# SniperBoard.net
KiCad netlist of a schematic drawn in EAGLE
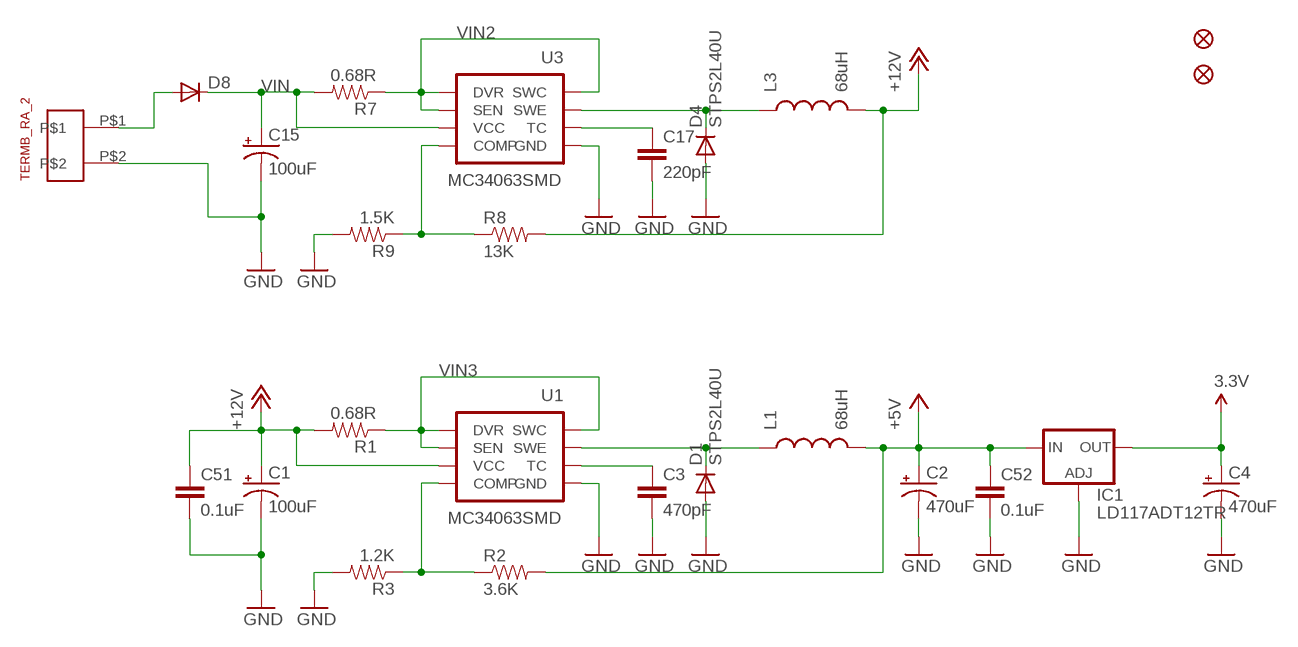
[diagram p0: schematic, sheet 1]
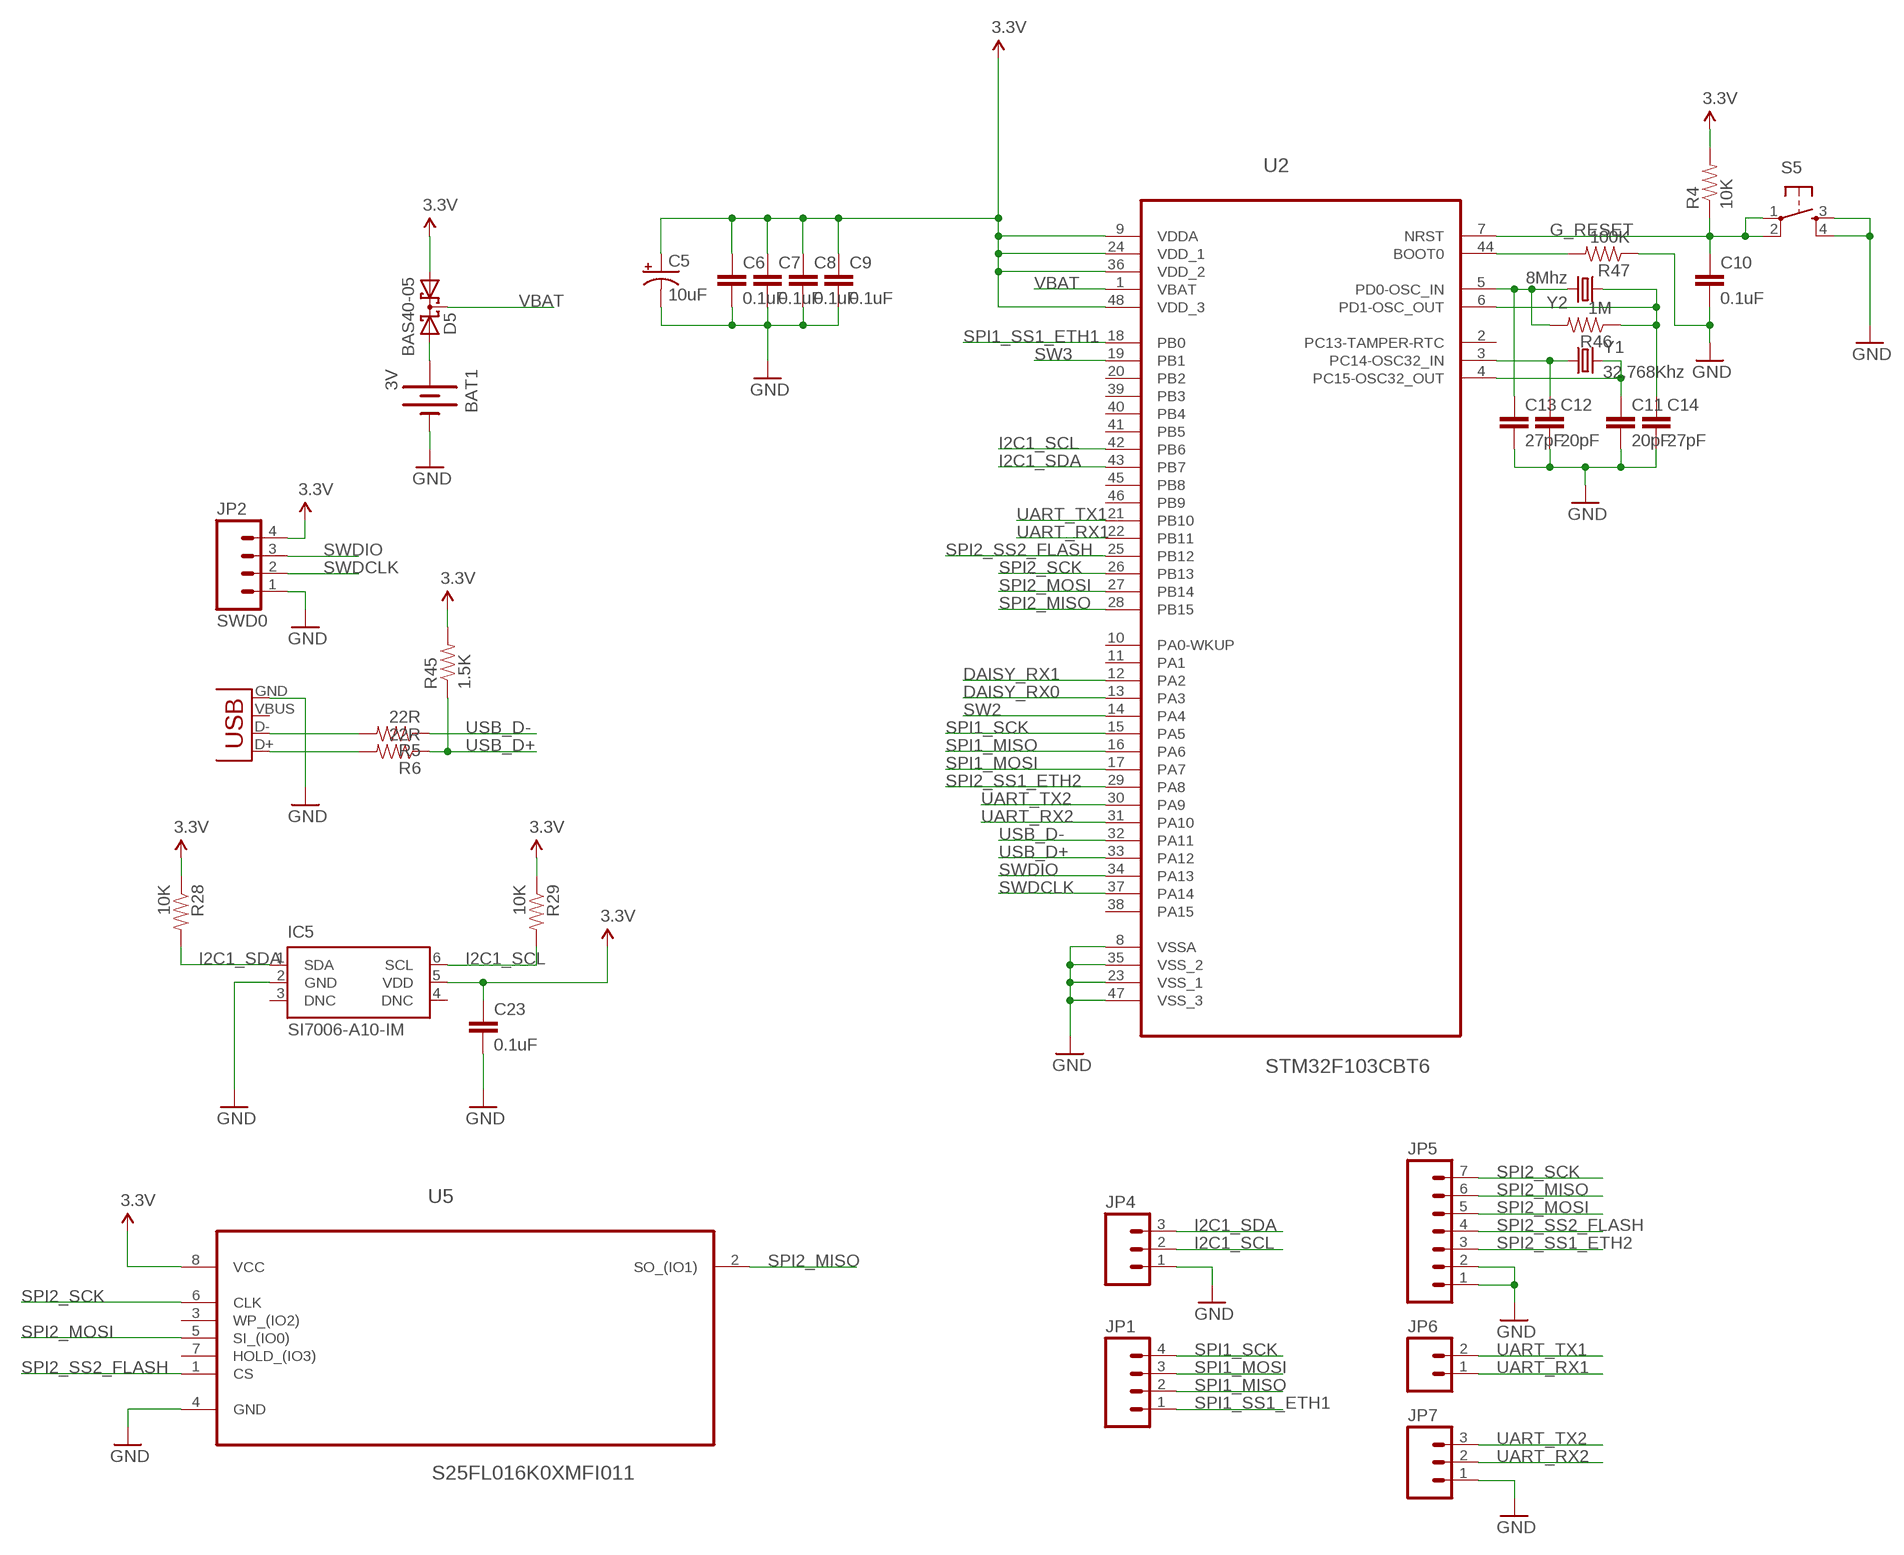
[diagram p1: schematic, sheet 2]
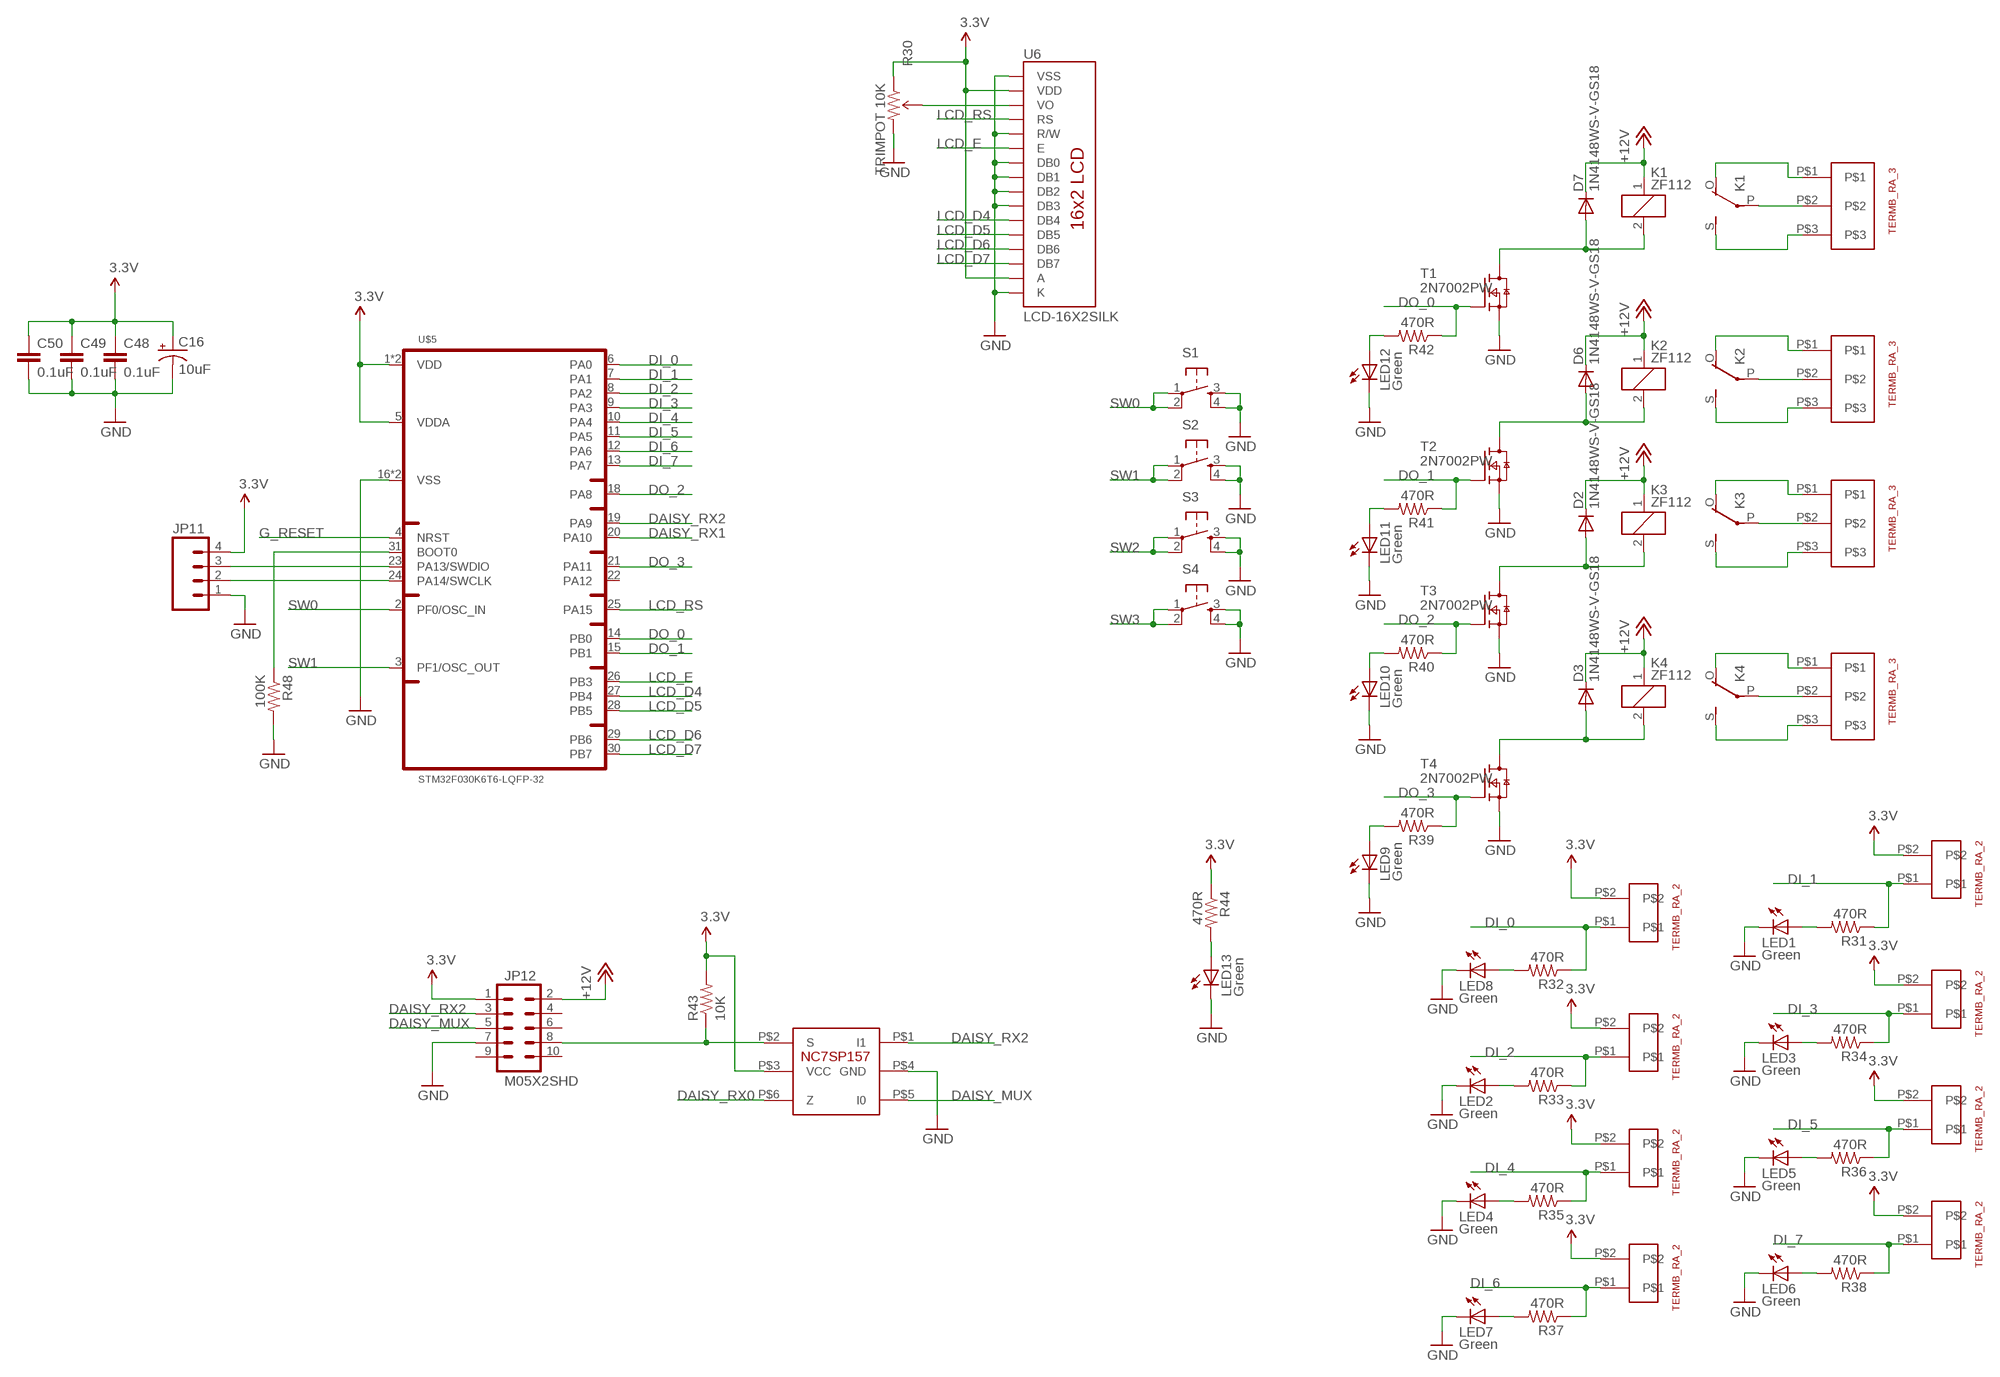
[diagram p2: schematic, sheet 3]
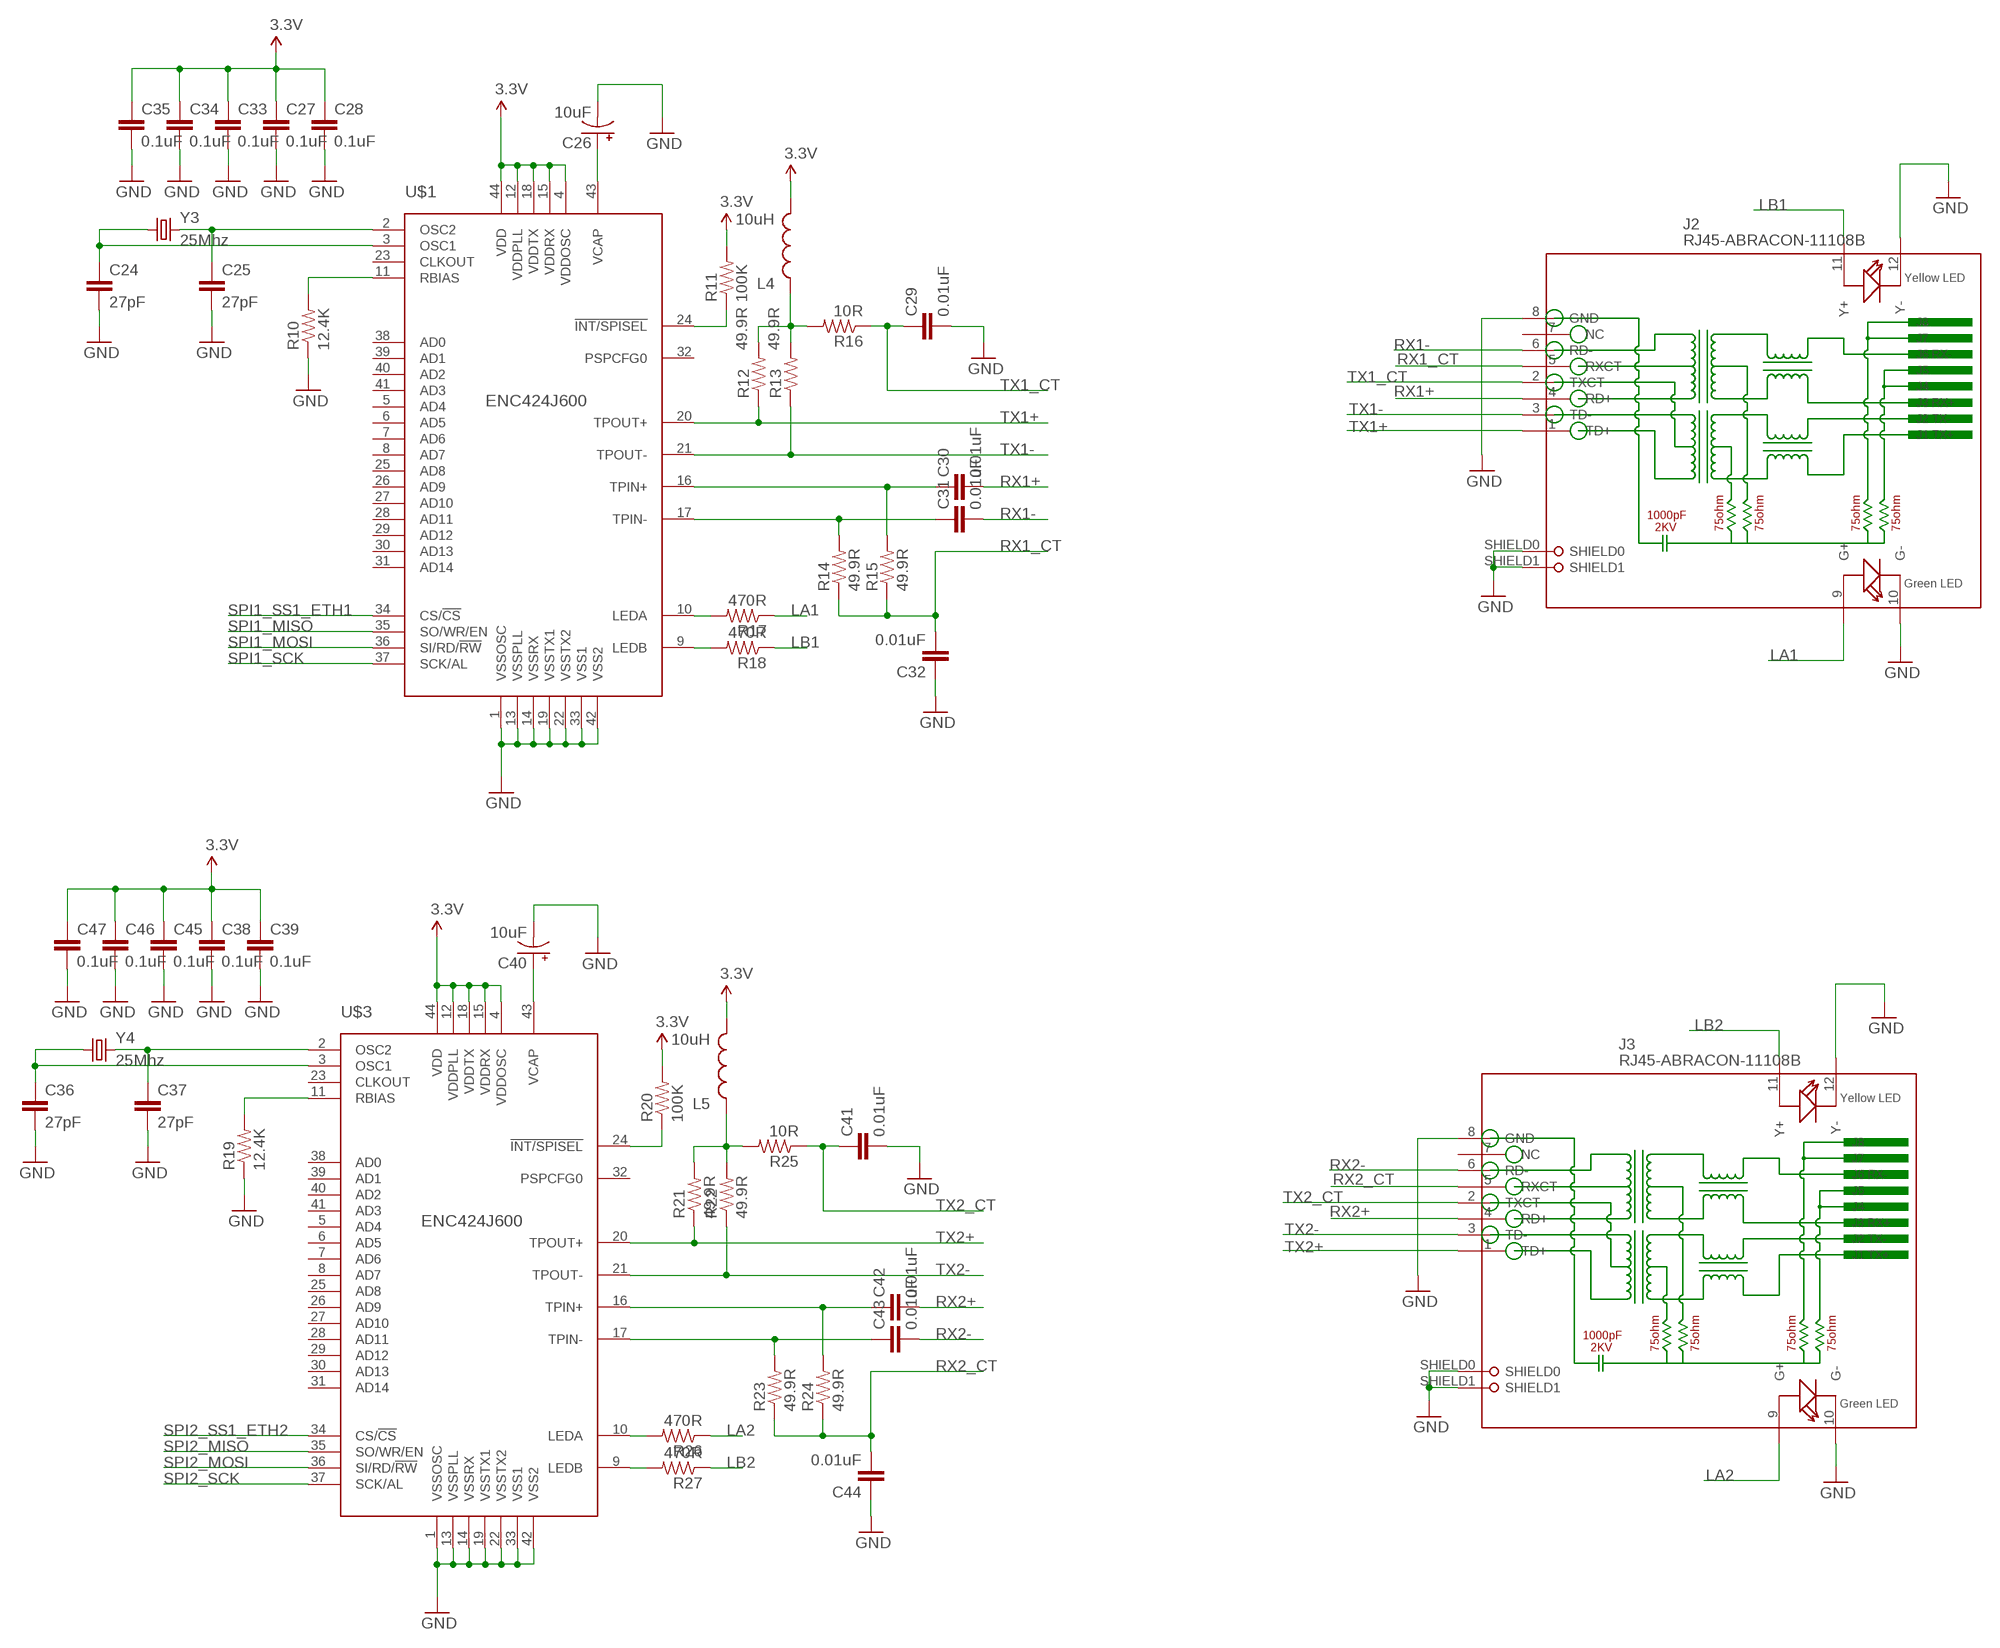
[diagram p3: schematic, sheet 4]
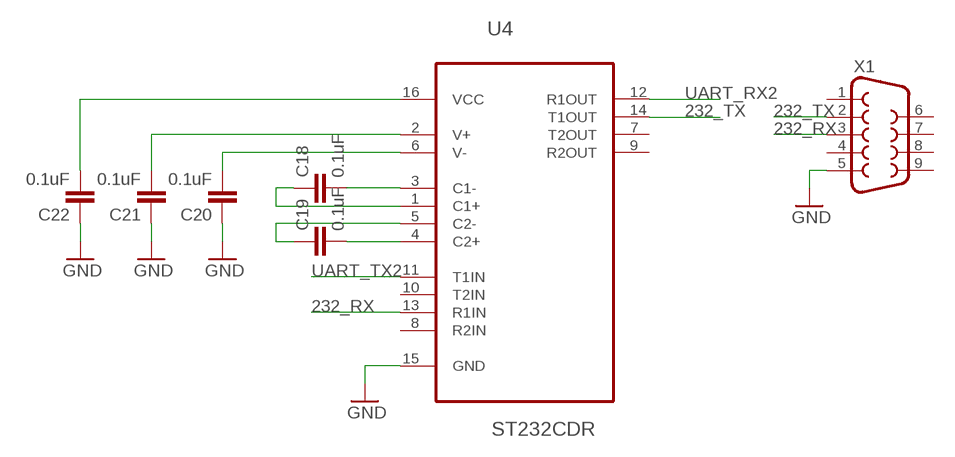
[diagram p4: schematic, sheet 5]

(export (version "E")
  (design (tool "Eeschema 10.0.6"))
  (components
    (comp (ref "C1")
      (value "100uF")
      (footprint "eagle-import:CPOL-RADIAL-100UF-25V")
      (libsource (lib "eagle-import") (part "CAP_POLPTH1"))
    )
    (comp (ref "C2")
      (value "470uF")
      (footprint "eagle-import:CPOL-RADIAL-100UF-25V")
      (libsource (lib "eagle-import") (part "CAP_POLPTH1"))
    )
    (comp (ref "C3")
      (value "470pF")
      (footprint "eagle-import:0805")
      (libsource (lib "eagle-import") (part "SparkFun-Passives_CAP0805"))
    )
    (comp (ref "C4")
      (value "470uF")
      (footprint "eagle-import:CPOL-RADIAL-100UF-25V")
      (libsource (lib "eagle-import") (part "CAP_POLPTH1"))
    )
    (comp (ref "C15")
      (value "100uF")
      (footprint "eagle-import:CPOL-RADIAL-100UF-25V")
      (libsource (lib "eagle-import") (part "CAP_POLPTH1"))
    )
    (comp (ref "C17")
      (value "220pF")
      (footprint "eagle-import:0805")
      (libsource (lib "eagle-import") (part "SparkFun-Passives_CAP0805"))
    )
    (comp (ref "C51")
      (value "0.1uF")
      (footprint "eagle-import:0805")
      (libsource (lib "eagle-import") (part "CAP0805"))
    )
    (comp (ref "C52")
      (value "0.1uF")
      (footprint "eagle-import:0805")
      (libsource (lib "eagle-import") (part "CAP0805"))
    )
    (comp (ref "D1")
      (value "STPS2L40U")
      (footprint "eagle-import:SMA-DIODE")
      (libsource (lib "eagle-import") (part "DIODESMA"))
    )
    (comp (ref "D4")
      (value "STPS2L40U")
      (footprint "eagle-import:SMA-DIODE")
      (libsource (lib "eagle-import") (part "DIODESMA"))
    )
    (comp (ref "D8")
      (value "DIODESMB")
      (footprint "eagle-import:SMB-DIODE")
      (libsource (lib "eagle-import") (part "DIODESMB"))
    )
    (comp (ref "FID1")
      (value "FIDUCIAL1.5X3")
      (footprint "eagle-import:FIDUCIAL-1.5X3")
      (libsource (lib "eagle-import") (part "FIDUCIAL1.5X3"))
    )
    (comp (ref "FID2")
      (value "FIDUCIAL1.5X3")
      (footprint "eagle-import:FIDUCIAL-1.5X3")
      (libsource (lib "eagle-import") (part "FIDUCIAL1.5X3"))
    )
    (comp (ref "IC1")
      (value "LD117ADT12TR")
      (footprint "eagle-import:DPACK")
      (libsource (lib "eagle-import") (part "LD117A?DT12TR"))
    )
    (comp (ref "L1")
      (value "68uH")
      (footprint "eagle-import:CDRH125")
      (libsource (lib "eagle-import") (part "INDUCTORPWR"))
    )
    (comp (ref "L3")
      (value "68uH")
      (footprint "eagle-import:CDRH125")
      (libsource (lib "eagle-import") (part "INDUCTORPWR"))
    )
    (comp (ref "R1")
      (value "0.68R")
      (footprint "eagle-import:0805")
      (libsource (lib "eagle-import") (part "RESISTOR0805-RES"))
    )
    (comp (ref "R2")
      (value "3.6K")
      (footprint "eagle-import:0805")
      (libsource (lib "eagle-import") (part "RESISTOR0805-RES"))
    )
    (comp (ref "R3")
      (value "1.2K")
      (footprint "eagle-import:0805")
      (libsource (lib "eagle-import") (part "RESISTOR0805-RES"))
    )
    (comp (ref "R7")
      (value "0.68R")
      (footprint "eagle-import:0805")
      (libsource (lib "eagle-import") (part "RESISTOR0805-RES"))
    )
    (comp (ref "R8")
      (value "13K")
      (footprint "eagle-import:0805")
      (libsource (lib "eagle-import") (part "RESISTOR0805-RES"))
    )
    (comp (ref "R9")
      (value "1.5K")
      (footprint "eagle-import:0805")
      (libsource (lib "eagle-import") (part "RESISTOR0805-RES"))
    )
    (comp (ref "U$2")
      (value "1X02_TERMB_RA")
      (footprint "eagle-import:1X02_TERMB_RA")
      (libsource (lib "eagle-import") (part "1X02_TERMB_RA"))
    )
    (comp (ref "U1")
      (value "MC34063SMD")
      (footprint "eagle-import:SO08")
      (libsource (lib "eagle-import") (part "MC34063SMD"))
    )
    (comp (ref "U3")
      (value "MC34063SMD")
      (footprint "eagle-import:SO08")
      (libsource (lib "eagle-import") (part "MC34063SMD"))
    )
    (comp (ref "C18")
      (value "0.1uF")
      (footprint "eagle-import:0805")
      (libsource (lib "eagle-import") (part "SparkFun-Passives_CAP0805"))
    )
    (comp (ref "C19")
      (value "0.1uF")
      (footprint "eagle-import:0805")
      (libsource (lib "eagle-import") (part "SparkFun-Passives_CAP0805"))
    )
    (comp (ref "C20")
      (value "0.1uF")
      (footprint "eagle-import:0805")
      (libsource (lib "eagle-import") (part "SparkFun-Passives_CAP0805"))
    )
    (comp (ref "C21")
      (value "0.1uF")
      (footprint "eagle-import:0805")
      (libsource (lib "eagle-import") (part "SparkFun-Passives_CAP0805"))
    )
    (comp (ref "C22")
      (value "0.1uF")
      (footprint "eagle-import:0805")
      (libsource (lib "eagle-import") (part "SparkFun-Passives_CAP0805"))
    )
    (comp (ref "U4")
      (value "ST232CDR")
      (footprint "eagle-import:SOIC127P600X175-16N")
      (libsource (lib "eagle-import") (part "ST232CDR"))
    )
    (comp (ref "X1")
      (value "DB9FEMALE")
      (footprint "eagle-import:DB9")
      (libsource (lib "eagle-import") (part "DB9FEMALE"))
    )
    (comp (ref "BAT1")
      (value "3V")
      (footprint "eagle-import:BATTCOM_20MM_PTH")
      (libsource (lib "eagle-import") (part "BATTERY20PTH"))
    )
    (comp (ref "C5")
      (value "10uF")
      (footprint "eagle-import:EIA3216")
      (libsource (lib "eagle-import") (part "10UF-TANT"))
    )
    (comp (ref "C6")
      (value "0.1uF")
      (footprint "eagle-import:0805")
      (libsource (lib "eagle-import") (part "CAP0805"))
    )
    (comp (ref "C7")
      (value "0.1uF")
      (footprint "eagle-import:0805")
      (libsource (lib "eagle-import") (part "CAP0805"))
    )
    (comp (ref "C8")
      (value "0.1uF")
      (footprint "eagle-import:0805")
      (libsource (lib "eagle-import") (part "CAP0805"))
    )
    (comp (ref "C9")
      (value "0.1uF")
      (footprint "eagle-import:0805")
      (libsource (lib "eagle-import") (part "CAP0805"))
    )
    (comp (ref "C10")
      (value "0.1uF")
      (footprint "eagle-import:0805")
      (libsource (lib "eagle-import") (part "CAP0805"))
    )
    (comp (ref "C11")
      (value "20pF")
      (footprint "eagle-import:0805")
      (libsource (lib "eagle-import") (part "CAP0805"))
    )
    (comp (ref "C12")
      (value "20pF")
      (footprint "eagle-import:0805")
      (libsource (lib "eagle-import") (part "CAP0805"))
    )
    (comp (ref "C13")
      (value "27pF")
      (footprint "eagle-import:0805")
      (libsource (lib "eagle-import") (part "CAP0805"))
    )
    (comp (ref "C14")
      (value "27pF")
      (footprint "eagle-import:0805")
      (libsource (lib "eagle-import") (part "CAP0805"))
    )
    (comp (ref "C23")
      (value "0.1uF")
      (footprint "eagle-import:0805")
      (libsource (lib "eagle-import") (part "CAP0805"))
    )
    (comp (ref "D5")
      (value "BAS40-05")
      (footprint "eagle-import:SOT23")
      (libsource (lib "eagle-import") (part "BAS40-05"))
    )
    (comp (ref "IC5")
      (value "SI7006-A10-IM")
      (footprint "eagle-import:DFN6-3X3")
      (fields (field (name "MF") "Silicon Labs") (field (name "MPN") "Si7006-A10-IM"))
      (libsource (lib "eagle-import") (part "SI7006-A10-IM"))
    )
    (comp (ref "JP1")
      (value "M04PTH")
      (footprint "eagle-import:1X04")
      (libsource (lib "eagle-import") (part "M04PTH"))
    )
    (comp (ref "JP2")
      (value "SWD0")
      (footprint "eagle-import:1X04")
      (libsource (lib "eagle-import") (part "M04PTH"))
    )
    (comp (ref "JP3")
      (value "USB-B")
      (footprint "eagle-import:USB-B-PTH")
      (libsource (lib "eagle-import") (part "USBPTH"))
    )
    (comp (ref "JP4")
      (value "M03PTH")
      (footprint "eagle-import:1X03")
      (libsource (lib "eagle-import") (part "M03PTH"))
    )
    (comp (ref "JP5")
      (value "M07")
      (footprint "eagle-import:1X07")
      (libsource (lib "eagle-import") (part "M07"))
    )
    (comp (ref "JP6")
      (value "M02PTH")
      (footprint "eagle-import:1X02")
      (libsource (lib "eagle-import") (part "M02PTH"))
    )
    (comp (ref "JP7")
      (value "M03PTH")
      (footprint "eagle-import:1X03")
      (libsource (lib "eagle-import") (part "M03PTH"))
    )
    (comp (ref "R4")
      (value "10K")
      (footprint "eagle-import:0805")
      (libsource (lib "eagle-import") (part "SparkFun-Resistors_RESISTOR0805-RES"))
    )
    (comp (ref "R5")
      (value "22R")
      (footprint "eagle-import:0805")
      (libsource (lib "eagle-import") (part "SparkFun-Resistors_RESISTOR0805-RES"))
    )
    (comp (ref "R6")
      (value "22R")
      (footprint "eagle-import:0805")
      (libsource (lib "eagle-import") (part "SparkFun-Resistors_RESISTOR0805-RES"))
    )
    (comp (ref "R28")
      (value "10K")
      (footprint "eagle-import:0805")
      (libsource (lib "eagle-import") (part "SparkFun-Resistors_RESISTOR0805-RES"))
    )
    (comp (ref "R29")
      (value "10K")
      (footprint "eagle-import:0805")
      (libsource (lib "eagle-import") (part "SparkFun-Resistors_RESISTOR0805-RES"))
    )
    (comp (ref "R45")
      (value "1.5K")
      (footprint "eagle-import:0805")
      (libsource (lib "eagle-import") (part "SparkFun-Resistors_RESISTOR0805-RES"))
    )
    (comp (ref "R46")
      (value "1M")
      (footprint "eagle-import:0805")
      (libsource (lib "eagle-import") (part "SparkFun-Resistors_RESISTOR0805-RES"))
    )
    (comp (ref "R47")
      (value "100K")
      (footprint "eagle-import:0805")
      (libsource (lib "eagle-import") (part "SparkFun-Resistors_RESISTOR0805-RES"))
    )
    (comp (ref "S5")
      (value "TAC_SWITCHPTH")
      (footprint "eagle-import:TACTILE-PTH")
      (libsource (lib "eagle-import") (part "TAC_SWITCHPTH"))
    )
    (comp (ref "U2")
      (value "STM32F103CBT6")
      (footprint "eagle-import:QFP50P900X900X160-48N")
      (libsource (lib "eagle-import") (part "STM32F103CBT6"))
    )
    (comp (ref "U5")
      (value "S25FL016K0XMFI011")
      (footprint "eagle-import:SOIC127P800X215-8N")
      (libsource (lib "eagle-import") (part "S25FL016K0XMFI011"))
    )
    (comp (ref "Y1")
      (value "32.768Khz")
      (footprint "eagle-import:MC-306")
      (fields (field (name "MPN") "MC-306 60.0KHZ  100PPM ,12.5PF"))
      (libsource (lib "eagle-import") (part "MC-306"))
    )
    (comp (ref "Y2")
      (value "8Mhz")
      (footprint "eagle-import:HC49US")
      (libsource (lib "eagle-import") (part "CRYSTALHC49US"))
    )
    (comp (ref "C16")
      (value "10uF")
      (footprint "eagle-import:EIA3216")
      (libsource (lib "eagle-import") (part "10UF-TANT"))
    )
    (comp (ref "C48")
      (value "0.1uF")
      (footprint "eagle-import:0805")
      (libsource (lib "eagle-import") (part "CAP0805"))
    )
    (comp (ref "C49")
      (value "0.1uF")
      (footprint "eagle-import:0805")
      (libsource (lib "eagle-import") (part "CAP0805"))
    )
    (comp (ref "C50")
      (value "0.1uF")
      (footprint "eagle-import:0805")
      (libsource (lib "eagle-import") (part "CAP0805"))
    )
    (comp (ref "D2")
      (value "1N4148WS-V-GS18")
      (footprint "eagle-import:SMA-DIODE_ALT")
      (libsource (lib "eagle-import") (part "DIODESMA-ALT"))
    )
    (comp (ref "D3")
      (value "1N4148WS-V-GS18")
      (footprint "eagle-import:SMA-DIODE_ALT")
      (libsource (lib "eagle-import") (part "DIODESMA-ALT"))
    )
    (comp (ref "D6")
      (value "1N4148WS-V-GS18")
      (footprint "eagle-import:SMA-DIODE_ALT")
      (libsource (lib "eagle-import") (part "DIODESMA-ALT"))
    )
    (comp (ref "D7")
      (value "1N4148WS-V-GS18")
      (footprint "eagle-import:SMA-DIODE_ALT")
      (libsource (lib "eagle-import") (part "DIODESMA-ALT"))
    )
    (comp (ref "JP11")
      (value "M04PTH")
      (footprint "eagle-import:1X04")
      (libsource (lib "eagle-import") (part "M04PTH"))
    )
    (comp (ref "JP12")
      (value "M05X2SHD")
      (footprint "eagle-import:2X5-SHROUDED")
      (libsource (lib "eagle-import") (part "M05X2SHD"))
    )
    (comp (ref "K1")
      (value "ZF112")
      (footprint "eagle-import:ZF112")
      (libsource (lib "eagle-import") (part "ZF112"))
    )
    (comp (ref "K2")
      (value "ZF112")
      (footprint "eagle-import:ZF112")
      (libsource (lib "eagle-import") (part "ZF112"))
    )
    (comp (ref "K3")
      (value "ZF112")
      (footprint "eagle-import:ZF112")
      (libsource (lib "eagle-import") (part "ZF112"))
    )
    (comp (ref "K4")
      (value "ZF112")
      (footprint "eagle-import:ZF112")
      (libsource (lib "eagle-import") (part "ZF112"))
    )
    (comp (ref "LED1")
      (value "Green")
      (footprint "eagle-import:LED-1206")
      (libsource (lib "eagle-import") (part "LED1206"))
    )
    (comp (ref "LED2")
      (value "Green")
      (footprint "eagle-import:LED-1206")
      (libsource (lib "eagle-import") (part "LED1206"))
    )
    (comp (ref "LED3")
      (value "Green")
      (footprint "eagle-import:LED-1206")
      (libsource (lib "eagle-import") (part "LED1206"))
    )
    (comp (ref "LED4")
      (value "Green")
      (footprint "eagle-import:LED-1206")
      (libsource (lib "eagle-import") (part "LED1206"))
    )
    (comp (ref "LED5")
      (value "Green")
      (footprint "eagle-import:LED-1206")
      (libsource (lib "eagle-import") (part "LED1206"))
    )
    (comp (ref "LED6")
      (value "Green")
      (footprint "eagle-import:LED-1206")
      (libsource (lib "eagle-import") (part "LED1206"))
    )
    (comp (ref "LED7")
      (value "Green")
      (footprint "eagle-import:LED-1206")
      (libsource (lib "eagle-import") (part "LED1206"))
    )
    (comp (ref "LED8")
      (value "Green")
      (footprint "eagle-import:LED-1206")
      (libsource (lib "eagle-import") (part "LED1206"))
    )
    (comp (ref "LED9")
      (value "Green")
      (footprint "eagle-import:LED-1206")
      (libsource (lib "eagle-import") (part "LED1206"))
    )
    (comp (ref "LED10")
      (value "Green")
      (footprint "eagle-import:LED-1206")
      (libsource (lib "eagle-import") (part "LED1206"))
    )
    (comp (ref "LED11")
      (value "Green")
      (footprint "eagle-import:LED-1206")
      (libsource (lib "eagle-import") (part "LED1206"))
    )
    (comp (ref "LED12")
      (value "Green")
      (footprint "eagle-import:LED-1206")
      (libsource (lib "eagle-import") (part "LED1206"))
    )
    (comp (ref "LED13")
      (value "Green")
      (footprint "eagle-import:LED-1206")
      (libsource (lib "eagle-import") (part "LED1206"))
    )
    (comp (ref "R30")
      (value "TRIMPOT 10K")
      (footprint "eagle-import:TRIM_POT_PTH")
      (libsource (lib "eagle-import") (part "TRIMPOTPTH"))
    )
    (comp (ref "R31")
      (value "470R")
      (footprint "eagle-import:0805")
      (libsource (lib "eagle-import") (part "RESISTOR0805-RES"))
    )
    (comp (ref "R32")
      (value "470R")
      (footprint "eagle-import:0805")
      (libsource (lib "eagle-import") (part "RESISTOR0805-RES"))
    )
    (comp (ref "R33")
      (value "470R")
      (footprint "eagle-import:0805")
      (libsource (lib "eagle-import") (part "RESISTOR0805-RES"))
    )
    (comp (ref "R34")
      (value "470R")
      (footprint "eagle-import:0805")
      (libsource (lib "eagle-import") (part "RESISTOR0805-RES"))
    )
    (comp (ref "R35")
      (value "470R")
      (footprint "eagle-import:0805")
      (libsource (lib "eagle-import") (part "RESISTOR0805-RES"))
    )
    (comp (ref "R36")
      (value "470R")
      (footprint "eagle-import:0805")
      (libsource (lib "eagle-import") (part "RESISTOR0805-RES"))
    )
    (comp (ref "R37")
      (value "470R")
      (footprint "eagle-import:0805")
      (libsource (lib "eagle-import") (part "RESISTOR0805-RES"))
    )
    (comp (ref "R38")
      (value "470R")
      (footprint "eagle-import:0805")
      (libsource (lib "eagle-import") (part "RESISTOR0805-RES"))
    )
    (comp (ref "R39")
      (value "470R")
      (footprint "eagle-import:0805")
      (libsource (lib "eagle-import") (part "RESISTOR0805-RES"))
    )
    (comp (ref "R40")
      (value "470R")
      (footprint "eagle-import:0805")
      (libsource (lib "eagle-import") (part "RESISTOR0805-RES"))
    )
    (comp (ref "R41")
      (value "470R")
      (footprint "eagle-import:0805")
      (libsource (lib "eagle-import") (part "RESISTOR0805-RES"))
    )
    (comp (ref "R42")
      (value "470R")
      (footprint "eagle-import:0805")
      (libsource (lib "eagle-import") (part "RESISTOR0805-RES"))
    )
    (comp (ref "R43")
      (value "10K")
      (footprint "eagle-import:0805")
      (libsource (lib "eagle-import") (part "RESISTOR0805-RES"))
    )
    (comp (ref "R44")
      (value "470R")
      (footprint "eagle-import:0805")
      (libsource (lib "eagle-import") (part "RESISTOR0805-RES"))
    )
    (comp (ref "R48")
      (value "100K")
      (footprint "eagle-import:0805")
      (libsource (lib "eagle-import") (part "RESISTOR0805-RES"))
    )
    (comp (ref "S1")
      (value "TAC_SWITCHPTH")
      (footprint "eagle-import:TACTILE-PTH")
      (libsource (lib "eagle-import") (part "TAC_SWITCHPTH"))
    )
    (comp (ref "S2")
      (value "TAC_SWITCHPTH")
      (footprint "eagle-import:TACTILE-PTH")
      (libsource (lib "eagle-import") (part "TAC_SWITCHPTH"))
    )
    (comp (ref "S3")
      (value "TAC_SWITCHPTH")
      (footprint "eagle-import:TACTILE-PTH")
      (libsource (lib "eagle-import") (part "TAC_SWITCHPTH"))
    )
    (comp (ref "S4")
      (value "TAC_SWITCHPTH")
      (footprint "eagle-import:TACTILE-PTH")
      (libsource (lib "eagle-import") (part "TAC_SWITCHPTH"))
    )
    (comp (ref "T1")
      (value "2N7002PW")
      (footprint "eagle-import:SOT323")
      (libsource (lib "eagle-import") (part "2N7002PW"))
    )
    (comp (ref "T2")
      (value "2N7002PW")
      (footprint "eagle-import:SOT323")
      (libsource (lib "eagle-import") (part "2N7002PW"))
    )
    (comp (ref "T3")
      (value "2N7002PW")
      (footprint "eagle-import:SOT323")
      (libsource (lib "eagle-import") (part "2N7002PW"))
    )
    (comp (ref "T4")
      (value "2N7002PW")
      (footprint "eagle-import:SOT323")
      (libsource (lib "eagle-import") (part "2N7002PW"))
    )
    (comp (ref "U$4")
      (value "NC7SP157")
      (footprint "eagle-import:SC70-6")
      (libsource (lib "eagle-import") (part "NC7SP157"))
    )
    (comp (ref "U$5")
      (value "STM32F030K6T6-LQFP-32")
      (footprint "eagle-import:LQFP-32")
      (libsource (lib "eagle-import") (part "STM32F030K6T6-LQFP-32"))
    )
    (comp (ref "U$6")
      (value "1X02_TERMB_RA")
      (footprint "eagle-import:1X02_TERMB_RA")
      (libsource (lib "eagle-import") (part "1X02_TERMB_RA"))
    )
    (comp (ref "U$7")
      (value "1X02_TERMB_RA")
      (footprint "eagle-import:1X02_TERMB_RA")
      (libsource (lib "eagle-import") (part "1X02_TERMB_RA"))
    )
    (comp (ref "U$8")
      (value "1X02_TERMB_RA")
      (footprint "eagle-import:1X02_TERMB_RA")
      (libsource (lib "eagle-import") (part "1X02_TERMB_RA"))
    )
    (comp (ref "U$9")
      (value "1X02_TERMB_RA")
      (footprint "eagle-import:1X02_TERMB_RA")
      (libsource (lib "eagle-import") (part "1X02_TERMB_RA"))
    )
    (comp (ref "U$10")
      (value "1X02_TERMB_RA")
      (footprint "eagle-import:1X02_TERMB_RA")
      (libsource (lib "eagle-import") (part "1X02_TERMB_RA"))
    )
    (comp (ref "U$11")
      (value "1X02_TERMB_RA")
      (footprint "eagle-import:1X02_TERMB_RA")
      (libsource (lib "eagle-import") (part "1X02_TERMB_RA"))
    )
    (comp (ref "U$12")
      (value "1X02_TERMB_RA")
      (footprint "eagle-import:1X02_TERMB_RA")
      (libsource (lib "eagle-import") (part "1X02_TERMB_RA"))
    )
    (comp (ref "U$13")
      (value "1X02_TERMB_RA")
      (footprint "eagle-import:1X02_TERMB_RA")
      (libsource (lib "eagle-import") (part "1X02_TERMB_RA"))
    )
    (comp (ref "U$14")
      (value "1X03_TERMB_RA")
      (footprint "eagle-import:1X03_TERMB_RA")
      (libsource (lib "eagle-import") (part "1X03_TERMB_RA"))
    )
    (comp (ref "U$15")
      (value "1X03_TERMB_RA")
      (footprint "eagle-import:1X03_TERMB_RA")
      (libsource (lib "eagle-import") (part "1X03_TERMB_RA"))
    )
    (comp (ref "U$16")
      (value "1X03_TERMB_RA")
      (footprint "eagle-import:1X03_TERMB_RA")
      (libsource (lib "eagle-import") (part "1X03_TERMB_RA"))
    )
    (comp (ref "U$17")
      (value "1X03_TERMB_RA")
      (footprint "eagle-import:1X03_TERMB_RA")
      (libsource (lib "eagle-import") (part "1X03_TERMB_RA"))
    )
    (comp (ref "U6")
      (value "LCD-16X2SILK")
      (footprint "eagle-import:LCD-16X2")
      (libsource (lib "eagle-import") (part "LCD-16X2SILK"))
    )
    (comp (ref "C24")
      (value "27pF")
      (footprint "eagle-import:0805")
      (libsource (lib "eagle-import") (part "CAP0805"))
    )
    (comp (ref "C25")
      (value "27pF")
      (footprint "eagle-import:0805")
      (libsource (lib "eagle-import") (part "CAP0805"))
    )
    (comp (ref "C26")
      (value "10uF")
      (footprint "eagle-import:EIA3528-KIT")
      (libsource (lib "eagle-import") (part "CAP_POL3528-KIT"))
    )
    (comp (ref "C27")
      (value "0.1uF")
      (footprint "eagle-import:0805")
      (libsource (lib "eagle-import") (part "CAP0805"))
    )
    (comp (ref "C28")
      (value "0.1uF")
      (footprint "eagle-import:0805")
      (libsource (lib "eagle-import") (part "CAP0805"))
    )
    (comp (ref "C29")
      (value "0.01uF")
      (footprint "eagle-import:0805")
      (libsource (lib "eagle-import") (part "CAP0805"))
    )
    (comp (ref "C30")
      (value "0.01uF")
      (footprint "eagle-import:0805")
      (libsource (lib "eagle-import") (part "CAP0805"))
    )
    (comp (ref "C31")
      (value "0.01uF")
      (footprint "eagle-import:0805")
      (libsource (lib "eagle-import") (part "CAP0805"))
    )
    (comp (ref "C32")
      (value "0.01uF")
      (footprint "eagle-import:0805")
      (libsource (lib "eagle-import") (part "CAP0805"))
    )
    (comp (ref "C33")
      (value "0.1uF")
      (footprint "eagle-import:0805")
      (libsource (lib "eagle-import") (part "CAP0805"))
    )
    (comp (ref "C34")
      (value "0.1uF")
      (footprint "eagle-import:0805")
      (libsource (lib "eagle-import") (part "CAP0805"))
    )
    (comp (ref "C35")
      (value "0.1uF")
      (footprint "eagle-import:0805")
      (libsource (lib "eagle-import") (part "CAP0805"))
    )
    (comp (ref "C36")
      (value "27pF")
      (footprint "eagle-import:0805")
      (libsource (lib "eagle-import") (part "CAP0805"))
    )
    (comp (ref "C37")
      (value "27pF")
      (footprint "eagle-import:0805")
      (libsource (lib "eagle-import") (part "CAP0805"))
    )
    (comp (ref "C38")
      (value "0.1uF")
      (footprint "eagle-import:0805")
      (libsource (lib "eagle-import") (part "CAP0805"))
    )
    (comp (ref "C39")
      (value "0.1uF")
      (footprint "eagle-import:0805")
      (libsource (lib "eagle-import") (part "CAP0805"))
    )
    (comp (ref "C40")
      (value "10uF")
      (footprint "eagle-import:EIA3528-KIT")
      (libsource (lib "eagle-import") (part "CAP_POL3528-KIT"))
    )
    (comp (ref "C41")
      (value "0.01uF")
      (footprint "eagle-import:0805")
      (libsource (lib "eagle-import") (part "CAP0805"))
    )
    (comp (ref "C42")
      (value "0.01uF")
      (footprint "eagle-import:0805")
      (libsource (lib "eagle-import") (part "CAP0805"))
    )
    (comp (ref "C43")
      (value "0.01uF")
      (footprint "eagle-import:0805")
      (libsource (lib "eagle-import") (part "CAP0805"))
    )
    (comp (ref "C44")
      (value "0.01uF")
      (footprint "eagle-import:0805")
      (libsource (lib "eagle-import") (part "CAP0805"))
    )
    (comp (ref "C45")
      (value "0.1uF")
      (footprint "eagle-import:0805")
      (libsource (lib "eagle-import") (part "CAP0805"))
    )
    (comp (ref "C46")
      (value "0.1uF")
      (footprint "eagle-import:0805")
      (libsource (lib "eagle-import") (part "CAP0805"))
    )
    (comp (ref "C47")
      (value "0.1uF")
      (footprint "eagle-import:0805")
      (libsource (lib "eagle-import") (part "CAP0805"))
    )
    (comp (ref "J2")
      (value "RJ45-ABRACON-11108B")
      (footprint "eagle-import:RJ45-ABRACON-111008B")
      (libsource (lib "eagle-import") (part "RJ45-ABRACON-11108B"))
    )
    (comp (ref "J3")
      (value "RJ45-ABRACON-11108B")
      (footprint "eagle-import:RJ45-ABRACON-111008B")
      (libsource (lib "eagle-import") (part "RJ45-ABRACON-11108B"))
    )
    (comp (ref "L4")
      (value "10uH")
      (footprint "eagle-import:0805")
      (libsource (lib "eagle-import") (part "INDUCTOR0805"))
    )
    (comp (ref "L5")
      (value "10uH")
      (footprint "eagle-import:0805")
      (libsource (lib "eagle-import") (part "INDUCTOR0805"))
    )
    (comp (ref "R10")
      (value "12.4K")
      (footprint "eagle-import:0805")
      (libsource (lib "eagle-import") (part "SparkFun-Resistors_RESISTOR0805-RES"))
    )
    (comp (ref "R11")
      (value "100K")
      (footprint "eagle-import:0805")
      (libsource (lib "eagle-import") (part "SparkFun-Resistors_RESISTOR0805-RES"))
    )
    (comp (ref "R12")
      (value "49.9R")
      (footprint "eagle-import:0805")
      (libsource (lib "eagle-import") (part "SparkFun-Resistors_RESISTOR0805-RES"))
    )
    (comp (ref "R13")
      (value "49.9R")
      (footprint "eagle-import:0805")
      (libsource (lib "eagle-import") (part "SparkFun-Resistors_RESISTOR0805-RES"))
    )
    (comp (ref "R14")
      (value "49.9R")
      (footprint "eagle-import:0805")
      (libsource (lib "eagle-import") (part "SparkFun-Resistors_RESISTOR0805-RES"))
    )
    (comp (ref "R15")
      (value "49.9R")
      (footprint "eagle-import:0805")
      (libsource (lib "eagle-import") (part "SparkFun-Resistors_RESISTOR0805-RES"))
    )
    (comp (ref "R16")
      (value "10R")
      (footprint "eagle-import:0805")
      (libsource (lib "eagle-import") (part "SparkFun-Resistors_RESISTOR0805-RES"))
    )
    (comp (ref "R17")
      (value "470R")
      (footprint "eagle-import:0805")
      (libsource (lib "eagle-import") (part "SparkFun-Resistors_RESISTOR0805-RES"))
    )
    (comp (ref "R18")
      (value "470R")
      (footprint "eagle-import:0805")
      (libsource (lib "eagle-import") (part "SparkFun-Resistors_RESISTOR0805-RES"))
    )
    (comp (ref "R19")
      (value "12.4K")
      (footprint "eagle-import:0805")
      (libsource (lib "eagle-import") (part "SparkFun-Resistors_RESISTOR0805-RES"))
    )
    (comp (ref "R20")
      (value "100K")
      (footprint "eagle-import:0805")
      (libsource (lib "eagle-import") (part "SparkFun-Resistors_RESISTOR0805-RES"))
    )
    (comp (ref "R21")
      (value "49.9R")
      (footprint "eagle-import:0805")
      (libsource (lib "eagle-import") (part "SparkFun-Resistors_RESISTOR0805-RES"))
    )
    (comp (ref "R22")
      (value "49.9R")
      (footprint "eagle-import:0805")
      (libsource (lib "eagle-import") (part "SparkFun-Resistors_RESISTOR0805-RES"))
    )
    (comp (ref "R23")
      (value "49.9R")
      (footprint "eagle-import:0805")
      (libsource (lib "eagle-import") (part "SparkFun-Resistors_RESISTOR0805-RES"))
    )
    (comp (ref "R24")
      (value "49.9R")
      (footprint "eagle-import:0805")
      (libsource (lib "eagle-import") (part "SparkFun-Resistors_RESISTOR0805-RES"))
    )
    (comp (ref "R25")
      (value "10R")
      (footprint "eagle-import:0805")
      (libsource (lib "eagle-import") (part "SparkFun-Resistors_RESISTOR0805-RES"))
    )
    (comp (ref "R26")
      (value "470R")
      (footprint "eagle-import:0805")
      (libsource (lib "eagle-import") (part "SparkFun-Resistors_RESISTOR0805-RES"))
    )
    (comp (ref "R27")
      (value "470R")
      (footprint "eagle-import:0805")
      (libsource (lib "eagle-import") (part "SparkFun-Resistors_RESISTOR0805-RES"))
    )
    (comp (ref "U$1")
      (value "ENC424J600")
      (footprint "eagle-import:TQFP-44")
      (libsource (lib "eagle-import") (part "ENC424J600"))
    )
    (comp (ref "U$3")
      (value "ENC424J600")
      (footprint "eagle-import:TQFP-44")
      (libsource (lib "eagle-import") (part "ENC424J600"))
    )
    (comp (ref "Y3")
      (value "25Mhz")
      (footprint "eagle-import:CRYSTAL-SMD-10.5X4.8-2PIN")
      (libsource (lib "eagle-import") (part "CRYSTAL10.5X4.8"))
    )
    (comp (ref "Y4")
      (value "25Mhz")
      (footprint "eagle-import:CRYSTAL-SMD-10.5X4.8-2PIN")
      (libsource (lib "eagle-import") (part "CRYSTAL10.5X4.8"))
    )
  )
  (nets
    (net (code "1") (name "+5V") (class "Default")
      (node (ref "C2") (pin "1") (pinfunction "+_1") (pintype "passive"))
      (node (ref "C52") (pin "1") (pinfunction "1_1") (pintype "passive"))
      (node (ref "IC1") (pin "3") (pinfunction "IN_3") (pintype "input"))
      (node (ref "L1") (pin "2") (pinfunction "2_2") (pintype "passive"))
      (node (ref "R2") (pin "2") (pinfunction "2_2") (pintype "passive"))
    )
    (net (code "2") (name "+12V") (class "Default")
      (node (ref "C1") (pin "1") (pinfunction "+_1") (pintype "passive"))
      (node (ref "C51") (pin "1") (pinfunction "1_1") (pintype "passive"))
      (node (ref "D2") (pin "C") (pinfunction "C_C") (pintype "passive"))
      (node (ref "D3") (pin "C") (pinfunction "C_C") (pintype "passive"))
      (node (ref "D6") (pin "C") (pinfunction "C_C") (pintype "passive"))
      (node (ref "D7") (pin "C") (pinfunction "C_C") (pintype "passive"))
      (node (ref "JP12") (pin "2") (pinfunction "2_2") (pintype "passive"))
      (node (ref "K1") (pin "1") (pinfunction "1_1") (pintype "passive"))
      (node (ref "K2") (pin "1") (pinfunction "1_1") (pintype "passive"))
      (node (ref "K3") (pin "1") (pinfunction "1_1") (pintype "passive"))
      (node (ref "K4") (pin "1") (pinfunction "1_1") (pintype "passive"))
      (node (ref "L3") (pin "2") (pinfunction "2_2") (pintype "passive"))
      (node (ref "R1") (pin "2") (pinfunction "2_2") (pintype "passive"))
      (node (ref "R8") (pin "2") (pinfunction "2_2") (pintype "passive"))
      (node (ref "U1") (pin "6") (pinfunction "VCC_6") (pintype "bidirectional"))
    )
    (net (code "3") (name "3.3V") (class "Default")
      (node (ref "C16") (pin "A") (pinfunction "+_A") (pintype "passive"))
      (node (ref "C23") (pin "1") (pinfunction "1_1") (pintype "passive"))
      (node (ref "C27") (pin "1") (pinfunction "1_1") (pintype "passive"))
      (node (ref "C28") (pin "1") (pinfunction "1_1") (pintype "passive"))
      (node (ref "C33") (pin "1") (pinfunction "1_1") (pintype "passive"))
      (node (ref "C34") (pin "1") (pinfunction "1_1") (pintype "passive"))
      (node (ref "C35") (pin "1") (pinfunction "1_1") (pintype "passive"))
      (node (ref "C38") (pin "1") (pinfunction "1_1") (pintype "passive"))
      (node (ref "C39") (pin "1") (pinfunction "1_1") (pintype "passive"))
      (node (ref "C4") (pin "1") (pinfunction "+_1") (pintype "passive"))
      (node (ref "C45") (pin "1") (pinfunction "1_1") (pintype "passive"))
      (node (ref "C46") (pin "1") (pinfunction "1_1") (pintype "passive"))
      (node (ref "C47") (pin "1") (pinfunction "1_1") (pintype "passive"))
      (node (ref "C48") (pin "1") (pinfunction "1_1") (pintype "passive"))
      (node (ref "C49") (pin "1") (pinfunction "1_1") (pintype "passive"))
      (node (ref "C5") (pin "A") (pinfunction "+_A") (pintype "passive"))
      (node (ref "C50") (pin "1") (pinfunction "1_1") (pintype "passive"))
      (node (ref "C6") (pin "1") (pinfunction "1_1") (pintype "passive"))
      (node (ref "C7") (pin "1") (pinfunction "1_1") (pintype "passive"))
      (node (ref "C8") (pin "1") (pinfunction "1_1") (pintype "passive"))
      (node (ref "C9") (pin "1") (pinfunction "1_1") (pintype "passive"))
      (node (ref "D5") (pin "1") (pinfunction "A1_1") (pintype "passive"))
      (node (ref "IC1") (pin "4") (pinfunction "OUT_4") (pintype "passive"))
      (node (ref "IC5") (pin "5") (pinfunction "VDD_5") (pintype "power_in"))
      (node (ref "JP11") (pin "4") (pinfunction "4_4") (pintype "passive"))
      (node (ref "JP12") (pin "1") (pinfunction "1_1") (pintype "passive"))
      (node (ref "JP2") (pin "4") (pinfunction "4_4") (pintype "passive"))
      (node (ref "L4") (pin "2") (pinfunction "2_2") (pintype "passive"))
      (node (ref "L5") (pin "2") (pinfunction "2_2") (pintype "passive"))
      (node (ref "R11") (pin "2") (pinfunction "2_2") (pintype "passive"))
      (node (ref "R20") (pin "2") (pinfunction "2_2") (pintype "passive"))
      (node (ref "R28") (pin "1") (pinfunction "1_1") (pintype "passive"))
      (node (ref "R29") (pin "1") (pinfunction "1_1") (pintype "passive"))
      (node (ref "R30") (pin "1") (pinfunction "CCW_1") (pintype "passive"))
      (node (ref "R4") (pin "2") (pinfunction "2_2") (pintype "passive"))
      (node (ref "R43") (pin "2") (pinfunction "2_2") (pintype "passive"))
      (node (ref "R44") (pin "1") (pinfunction "1_1") (pintype "passive"))
      (node (ref "R45") (pin "2") (pinfunction "2_2") (pintype "passive"))
      (node (ref "U$1") (pin "12") (pinfunction "VDDPLL_12") (pintype "bidirectional"))
      (node (ref "U$1") (pin "15") (pinfunction "VDDRX_15") (pintype "bidirectional"))
      (node (ref "U$1") (pin "18") (pinfunction "VDDTX_18") (pintype "bidirectional"))
      (node (ref "U$1") (pin "4") (pinfunction "VDDOSC_4") (pintype "bidirectional"))
      (node (ref "U$1") (pin "44") (pinfunction "VDD_44") (pintype "bidirectional"))
      (node (ref "U$10") (pin "P$2") (pinfunction "P$2_P$2") (pintype "bidirectional"))
      (node (ref "U$11") (pin "P$2") (pinfunction "P$2_P$2") (pintype "bidirectional"))
      (node (ref "U$12") (pin "P$2") (pinfunction "P$2_P$2") (pintype "bidirectional"))
      (node (ref "U$13") (pin "P$2") (pinfunction "P$2_P$2") (pintype "bidirectional"))
      (node (ref "U$3") (pin "12") (pinfunction "VDDPLL_12") (pintype "bidirectional"))
      (node (ref "U$3") (pin "15") (pinfunction "VDDRX_15") (pintype "bidirectional"))
      (node (ref "U$3") (pin "18") (pinfunction "VDDTX_18") (pintype "bidirectional"))
      (node (ref "U$3") (pin "4") (pinfunction "VDDOSC_4") (pintype "bidirectional"))
      (node (ref "U$3") (pin "44") (pinfunction "VDD_44") (pintype "bidirectional"))
      (node (ref "U$4") (pin "P$3") (pinfunction "VCC_P$3") (pintype "bidirectional"))
      (node (ref "U$5") (pin "1") (pinfunction "VDD_1") (pintype "bidirectional"))
      (node (ref "U$5") (pin "17") (pinfunction "VDD_17") (pintype "bidirectional"))
      (node (ref "U$5") (pin "5") (pinfunction "VDDA_5") (pintype "bidirectional"))
      (node (ref "U$6") (pin "P$2") (pinfunction "P$2_P$2") (pintype "bidirectional"))
      (node (ref "U$7") (pin "P$2") (pinfunction "P$2_P$2") (pintype "bidirectional"))
      (node (ref "U$8") (pin "P$2") (pinfunction "P$2_P$2") (pintype "bidirectional"))
      (node (ref "U$9") (pin "P$2") (pinfunction "P$2_P$2") (pintype "bidirectional"))
      (node (ref "U2") (pin "24") (pinfunction "VDD_1_24") (pintype "bidirectional"))
      (node (ref "U2") (pin "36") (pinfunction "VDD_2_36") (pintype "power_in"))
      (node (ref "U2") (pin "48") (pinfunction "VDD_3_48") (pintype "power_in"))
      (node (ref "U2") (pin "9") (pinfunction "VDDA_9") (pintype "power_in"))
      (node (ref "U5") (pin "8") (pinfunction "VCC_8") (pintype "power_in"))
      (node (ref "U6") (pin "15") (pinfunction "A_15") (pintype "power_in"))
      (node (ref "U6") (pin "2") (pinfunction "VDD_2") (pintype "power_in"))
    )
    (net (code "4") (name "232_RX") (class "Default")
      (node (ref "U4") (pin "13") (pinfunction "R1IN_13") (pintype "input"))
      (node (ref "X1") (pin "3") (pinfunction "3_3") (pintype "passive"))
    )
    (net (code "5") (name "232_TX") (class "Default")
      (node (ref "U4") (pin "14") (pinfunction "T1OUT_14") (pintype "output"))
      (node (ref "X1") (pin "2") (pinfunction "2_2") (pintype "passive"))
    )
    (net (code "6") (name "DAISY_MUX") (class "Default")
      (node (ref "JP12") (pin "5") (pinfunction "5_5") (pintype "passive"))
      (node (ref "U$4") (pin "P$5") (pinfunction "I0_P$5") (pintype "bidirectional"))
    )
    (net (code "7") (name "DAISY_RX0") (class "Default")
      (node (ref "U$4") (pin "P$6") (pinfunction "Z_P$6") (pintype "bidirectional"))
      (node (ref "U2") (pin "13") (pinfunction "PA3_13") (pintype "bidirectional"))
    )
    (net (code "8") (name "DAISY_RX1") (class "Default")
      (node (ref "U$5") (pin "20") (pinfunction "PA10_20") (pintype "bidirectional"))
      (node (ref "U2") (pin "12") (pinfunction "PA2_12") (pintype "bidirectional"))
    )
    (net (code "9") (name "DAISY_RX2") (class "Default")
      (node (ref "JP12") (pin "3") (pinfunction "3_3") (pintype "passive"))
      (node (ref "U$4") (pin "P$1") (pinfunction "I1_P$1") (pintype "bidirectional"))
      (node (ref "U$5") (pin "19") (pinfunction "PA9_19") (pintype "bidirectional"))
    )
    (net (code "10") (name "DI_0") (class "Default")
      (node (ref "R32") (pin "1") (pinfunction "1_1") (pintype "passive"))
      (node (ref "U$5") (pin "6") (pinfunction "PA0_6") (pintype "bidirectional"))
      (node (ref "U$6") (pin "P$1") (pinfunction "P$1_P$1") (pintype "bidirectional"))
    )
    (net (code "11") (name "DI_1") (class "Default")
      (node (ref "R31") (pin "1") (pinfunction "1_1") (pintype "passive"))
      (node (ref "U$5") (pin "7") (pinfunction "PA1_7") (pintype "bidirectional"))
      (node (ref "U$7") (pin "P$1") (pinfunction "P$1_P$1") (pintype "bidirectional"))
    )
    (net (code "12") (name "DI_2") (class "Default")
      (node (ref "R33") (pin "1") (pinfunction "1_1") (pintype "passive"))
      (node (ref "U$13") (pin "P$1") (pinfunction "P$1_P$1") (pintype "bidirectional"))
      (node (ref "U$5") (pin "8") (pinfunction "PA2_8") (pintype "bidirectional"))
    )
    (net (code "13") (name "DI_3") (class "Default")
      (node (ref "R34") (pin "1") (pinfunction "1_1") (pintype "passive"))
      (node (ref "U$5") (pin "9") (pinfunction "PA3_9") (pintype "bidirectional"))
      (node (ref "U$8") (pin "P$1") (pinfunction "P$1_P$1") (pintype "bidirectional"))
    )
    (net (code "14") (name "DI_4") (class "Default")
      (node (ref "R35") (pin "1") (pinfunction "1_1") (pintype "passive"))
      (node (ref "U$12") (pin "P$1") (pinfunction "P$1_P$1") (pintype "bidirectional"))
      (node (ref "U$5") (pin "10") (pinfunction "PA4_10") (pintype "bidirectional"))
    )
    (net (code "15") (name "DI_5") (class "Default")
      (node (ref "R36") (pin "1") (pinfunction "1_1") (pintype "passive"))
      (node (ref "U$5") (pin "11") (pinfunction "PA5_11") (pintype "bidirectional"))
      (node (ref "U$9") (pin "P$1") (pinfunction "P$1_P$1") (pintype "bidirectional"))
    )
    (net (code "16") (name "DI_6") (class "Default")
      (node (ref "R37") (pin "1") (pinfunction "1_1") (pintype "passive"))
      (node (ref "U$11") (pin "P$1") (pinfunction "P$1_P$1") (pintype "bidirectional"))
      (node (ref "U$5") (pin "12") (pinfunction "PA6_12") (pintype "bidirectional"))
    )
    (net (code "17") (name "DI_7") (class "Default")
      (node (ref "R38") (pin "1") (pinfunction "1_1") (pintype "passive"))
      (node (ref "U$10") (pin "P$1") (pinfunction "P$1_P$1") (pintype "bidirectional"))
      (node (ref "U$5") (pin "13") (pinfunction "PA7_13") (pintype "bidirectional"))
    )
    (net (code "18") (name "DO_0") (class "Default")
      (node (ref "R42") (pin "1") (pinfunction "1_1") (pintype "passive"))
      (node (ref "T1") (pin "1") (pinfunction "G_1") (pintype "passive"))
      (node (ref "U$5") (pin "14") (pinfunction "PB0_14") (pintype "bidirectional"))
    )
    (net (code "19") (name "DO_1") (class "Default")
      (node (ref "R41") (pin "1") (pinfunction "1_1") (pintype "passive"))
      (node (ref "T2") (pin "1") (pinfunction "G_1") (pintype "passive"))
      (node (ref "U$5") (pin "15") (pinfunction "PB1_15") (pintype "bidirectional"))
    )
    (net (code "20") (name "DO_2") (class "Default")
      (node (ref "R40") (pin "1") (pinfunction "1_1") (pintype "passive"))
      (node (ref "T3") (pin "1") (pinfunction "G_1") (pintype "passive"))
      (node (ref "U$5") (pin "18") (pinfunction "PA8_18") (pintype "bidirectional"))
    )
    (net (code "21") (name "DO_3") (class "Default")
      (node (ref "R39") (pin "1") (pinfunction "1_1") (pintype "passive"))
      (node (ref "T4") (pin "1") (pinfunction "G_1") (pintype "passive"))
      (node (ref "U$5") (pin "21") (pinfunction "PA11_21") (pintype "bidirectional"))
    )
    (net (code "22") (name "GND") (class "Default")
      (node (ref "BAT1") (pin "2") (pinfunction "-_2") (pintype "power_in"))
      (node (ref "C1") (pin "2") (pinfunction "-_2") (pintype "passive"))
      (node (ref "C10") (pin "2") (pinfunction "2_2") (pintype "passive"))
      (node (ref "C11") (pin "2") (pinfunction "2_2") (pintype "passive"))
      (node (ref "C12") (pin "2") (pinfunction "2_2") (pintype "passive"))
      (node (ref "C13") (pin "2") (pinfunction "2_2") (pintype "passive"))
      (node (ref "C14") (pin "2") (pinfunction "2_2") (pintype "passive"))
      (node (ref "C15") (pin "2") (pinfunction "-_2") (pintype "passive"))
      (node (ref "C16") (pin "C") (pinfunction "-_C") (pintype "passive"))
      (node (ref "C17") (pin "2") (pinfunction "2_2") (pintype "passive"))
      (node (ref "C2") (pin "2") (pinfunction "-_2") (pintype "passive"))
      (node (ref "C20") (pin "1") (pinfunction "1_1") (pintype "passive"))
      (node (ref "C21") (pin "1") (pinfunction "1_1") (pintype "passive"))
      (node (ref "C22") (pin "1") (pinfunction "1_1") (pintype "passive"))
      (node (ref "C23") (pin "2") (pinfunction "2_2") (pintype "passive"))
      (node (ref "C24") (pin "2") (pinfunction "2_2") (pintype "passive"))
      (node (ref "C25") (pin "2") (pinfunction "2_2") (pintype "passive"))
      (node (ref "C26") (pin "C") (pinfunction "-_C") (pintype "passive"))
      (node (ref "C27") (pin "2") (pinfunction "2_2") (pintype "passive"))
      (node (ref "C28") (pin "2") (pinfunction "2_2") (pintype "passive"))
      (node (ref "C29") (pin "2") (pinfunction "2_2") (pintype "passive"))
      (node (ref "C3") (pin "2") (pinfunction "2_2") (pintype "passive"))
      (node (ref "C32") (pin "1") (pinfunction "1_1") (pintype "passive"))
      (node (ref "C33") (pin "2") (pinfunction "2_2") (pintype "passive"))
      (node (ref "C34") (pin "2") (pinfunction "2_2") (pintype "passive"))
      (node (ref "C35") (pin "2") (pinfunction "2_2") (pintype "passive"))
      (node (ref "C36") (pin "2") (pinfunction "2_2") (pintype "passive"))
      (node (ref "C37") (pin "2") (pinfunction "2_2") (pintype "passive"))
      (node (ref "C38") (pin "2") (pinfunction "2_2") (pintype "passive"))
      (node (ref "C39") (pin "2") (pinfunction "2_2") (pintype "passive"))
      (node (ref "C4") (pin "2") (pinfunction "-_2") (pintype "passive"))
      (node (ref "C40") (pin "C") (pinfunction "-_C") (pintype "passive"))
      (node (ref "C41") (pin "2") (pinfunction "2_2") (pintype "passive"))
      (node (ref "C44") (pin "1") (pinfunction "1_1") (pintype "passive"))
      (node (ref "C45") (pin "2") (pinfunction "2_2") (pintype "passive"))
      (node (ref "C46") (pin "2") (pinfunction "2_2") (pintype "passive"))
      (node (ref "C47") (pin "2") (pinfunction "2_2") (pintype "passive"))
      (node (ref "C48") (pin "2") (pinfunction "2_2") (pintype "passive"))
      (node (ref "C49") (pin "2") (pinfunction "2_2") (pintype "passive"))
      (node (ref "C5") (pin "C") (pinfunction "-_C") (pintype "passive"))
      (node (ref "C50") (pin "2") (pinfunction "2_2") (pintype "passive"))
      (node (ref "C51") (pin "2") (pinfunction "2_2") (pintype "passive"))
      (node (ref "C52") (pin "2") (pinfunction "2_2") (pintype "passive"))
      (node (ref "C6") (pin "2") (pinfunction "2_2") (pintype "passive"))
      (node (ref "C7") (pin "2") (pinfunction "2_2") (pintype "passive"))
      (node (ref "C8") (pin "2") (pinfunction "2_2") (pintype "passive"))
      (node (ref "C9") (pin "2") (pinfunction "2_2") (pintype "passive"))
      (node (ref "D1") (pin "A") (pinfunction "A_A") (pintype "passive"))
      (node (ref "D4") (pin "A") (pinfunction "A_A") (pintype "passive"))
      (node (ref "IC1") (pin "1") (pinfunction "ADJ_1") (pintype "input"))
      (node (ref "IC5") (pin "2") (pinfunction "GND_2") (pintype "power_in"))
      (node (ref "J2") (pin "10") (pinfunction "G-_10") (pintype "bidirectional"))
      (node (ref "J2") (pin "12") (pinfunction "Y-_12") (pintype "bidirectional"))
      (node (ref "J2") (pin "8") (pinfunction "GND_8") (pintype "bidirectional"))
      (node (ref "J2") (pin "SHIELD0") (pinfunction "SHIELD0_SHIELD0") (pintype "bidirectional"))
      (node (ref "J2") (pin "SHIELD1") (pinfunction "SHIELD1_SHIELD1") (pintype "bidirectional"))
      (node (ref "J3") (pin "10") (pinfunction "G-_10") (pintype "bidirectional"))
      (node (ref "J3") (pin "12") (pinfunction "Y-_12") (pintype "bidirectional"))
      (node (ref "J3") (pin "8") (pinfunction "GND_8") (pintype "bidirectional"))
      (node (ref "J3") (pin "SHIELD0") (pinfunction "SHIELD0_SHIELD0") (pintype "bidirectional"))
      (node (ref "J3") (pin "SHIELD1") (pinfunction "SHIELD1_SHIELD1") (pintype "bidirectional"))
      (node (ref "JP11") (pin "1") (pinfunction "1_1") (pintype "passive"))
      (node (ref "JP12") (pin "7") (pinfunction "7_7") (pintype "passive"))
      (node (ref "JP2") (pin "1") (pinfunction "1_1") (pintype "passive"))
      (node (ref "JP3") (pin "GND") (pinfunction "GND_GND") (pintype "bidirectional"))
      (node (ref "JP4") (pin "1") (pinfunction "1_1") (pintype "passive"))
      (node (ref "JP5") (pin "1") (pinfunction "1_1") (pintype "passive"))
      (node (ref "JP5") (pin "2") (pinfunction "2_2") (pintype "passive"))
      (node (ref "JP7") (pin "1") (pinfunction "1_1") (pintype "passive"))
      (node (ref "LED1") (pin "C") (pinfunction "C_C") (pintype "passive"))
      (node (ref "LED10") (pin "C") (pinfunction "C_C") (pintype "passive"))
      (node (ref "LED11") (pin "C") (pinfunction "C_C") (pintype "passive"))
      (node (ref "LED12") (pin "C") (pinfunction "C_C") (pintype "passive"))
      (node (ref "LED13") (pin "C") (pinfunction "C_C") (pintype "passive"))
      (node (ref "LED2") (pin "C") (pinfunction "C_C") (pintype "passive"))
      (node (ref "LED3") (pin "C") (pinfunction "C_C") (pintype "passive"))
      (node (ref "LED4") (pin "C") (pinfunction "C_C") (pintype "passive"))
      (node (ref "LED5") (pin "C") (pinfunction "C_C") (pintype "passive"))
      (node (ref "LED6") (pin "C") (pinfunction "C_C") (pintype "passive"))
      (node (ref "LED7") (pin "C") (pinfunction "C_C") (pintype "passive"))
      (node (ref "LED8") (pin "C") (pinfunction "C_C") (pintype "passive"))
      (node (ref "LED9") (pin "C") (pinfunction "C_C") (pintype "passive"))
      (node (ref "R10") (pin "1") (pinfunction "1_1") (pintype "passive"))
      (node (ref "R19") (pin "1") (pinfunction "1_1") (pintype "passive"))
      (node (ref "R3") (pin "2") (pinfunction "2_2") (pintype "passive"))
      (node (ref "R30") (pin "3") (pinfunction "CW_3") (pintype "passive"))
      (node (ref "R47") (pin "1") (pinfunction "1_1") (pintype "passive"))
      (node (ref "R48") (pin "2") (pinfunction "2_2") (pintype "passive"))
      (node (ref "R9") (pin "2") (pinfunction "2_2") (pintype "passive"))
      (node (ref "S1") (pin "3") (pinfunction "3_3") (pintype "passive"))
      (node (ref "S1") (pin "4") (pinfunction "4_4") (pintype "passive"))
      (node (ref "S2") (pin "3") (pinfunction "3_3") (pintype "passive"))
      (node (ref "S2") (pin "4") (pinfunction "4_4") (pintype "passive"))
      (node (ref "S3") (pin "3") (pinfunction "3_3") (pintype "passive"))
      (node (ref "S3") (pin "4") (pinfunction "4_4") (pintype "passive"))
      (node (ref "S4") (pin "3") (pinfunction "3_3") (pintype "passive"))
      (node (ref "S4") (pin "4") (pinfunction "4_4") (pintype "passive"))
      (node (ref "S5") (pin "3") (pinfunction "3_3") (pintype "passive"))
      (node (ref "S5") (pin "4") (pinfunction "4_4") (pintype "passive"))
      (node (ref "T1") (pin "2") (pinfunction "S_2") (pintype "passive"))
      (node (ref "T2") (pin "2") (pinfunction "S_2") (pintype "passive"))
      (node (ref "T3") (pin "2") (pinfunction "S_2") (pintype "passive"))
      (node (ref "T4") (pin "2") (pinfunction "S_2") (pintype "passive"))
      (node (ref "U$1") (pin "1") (pinfunction "VSSOSC_1") (pintype "bidirectional"))
      (node (ref "U$1") (pin "13") (pinfunction "VSSPLL_13") (pintype "bidirectional"))
      (node (ref "U$1") (pin "14") (pinfunction "VSSRX_14") (pintype "bidirectional"))
      (node (ref "U$1") (pin "19") (pinfunction "VSSTX1_19") (pintype "bidirectional"))
      (node (ref "U$1") (pin "22") (pinfunction "VSSTX2_22") (pintype "bidirectional"))
      (node (ref "U$1") (pin "33") (pinfunction "VSS1_33") (pintype "bidirectional"))
      (node (ref "U$1") (pin "42") (pinfunction "VSS2_42") (pintype "bidirectional"))
      (node (ref "U$2") (pin "P$2") (pinfunction "P$2_P$2") (pintype "bidirectional"))
      (node (ref "U$3") (pin "1") (pinfunction "VSSOSC_1") (pintype "bidirectional"))
      (node (ref "U$3") (pin "13") (pinfunction "VSSPLL_13") (pintype "bidirectional"))
      (node (ref "U$3") (pin "14") (pinfunction "VSSRX_14") (pintype "bidirectional"))
      (node (ref "U$3") (pin "19") (pinfunction "VSSTX1_19") (pintype "bidirectional"))
      (node (ref "U$3") (pin "22") (pinfunction "VSSTX2_22") (pintype "bidirectional"))
      (node (ref "U$3") (pin "33") (pinfunction "VSS1_33") (pintype "bidirectional"))
      (node (ref "U$3") (pin "42") (pinfunction "VSS2_42") (pintype "bidirectional"))
      (node (ref "U$4") (pin "P$4") (pinfunction "GND_P$4") (pintype "bidirectional"))
      (node (ref "U$5") (pin "16") (pinfunction "VSS_16") (pintype "bidirectional"))
      (node (ref "U$5") (pin "32") (pinfunction "VSS_32") (pintype "bidirectional"))
      (node (ref "U1") (pin "4") (pinfunction "GND_4") (pintype "bidirectional"))
      (node (ref "U2") (pin "23") (pinfunction "VSS_1_23") (pintype "bidirectional"))
      (node (ref "U2") (pin "35") (pinfunction "VSS_2_35") (pintype "passive"))
      (node (ref "U2") (pin "47") (pinfunction "VSS_3_47") (pintype "passive"))
      (node (ref "U2") (pin "8") (pinfunction "VSSA_8") (pintype "passive"))
      (node (ref "U3") (pin "4") (pinfunction "GND_4") (pintype "bidirectional"))
      (node (ref "U4") (pin "15") (pinfunction "GND_15") (pintype "passive"))
      (node (ref "U5") (pin "4") (pinfunction "GND_4") (pintype "passive"))
      (node (ref "U6") (pin "1") (pinfunction "VSS_1") (pintype "power_in"))
      (node (ref "U6") (pin "10") (pinfunction "DB3_10") (pintype "bidirectional"))
      (node (ref "U6") (pin "16") (pinfunction "K_16") (pintype "power_in"))
      (node (ref "U6") (pin "5") (pinfunction "R/W_5") (pintype "input"))
      (node (ref "U6") (pin "7") (pinfunction "DB0_7") (pintype "bidirectional"))
      (node (ref "U6") (pin "8") (pinfunction "DB1_8") (pintype "bidirectional"))
      (node (ref "U6") (pin "9") (pinfunction "DB2_9") (pintype "bidirectional"))
      (node (ref "X1") (pin "5") (pinfunction "5_5") (pintype "passive"))
    )
    (net (code "23") (name "G_RESET") (class "Default")
      (node (ref "C10") (pin "1") (pinfunction "1_1") (pintype "passive"))
      (node (ref "R4") (pin "1") (pinfunction "1_1") (pintype "passive"))
      (node (ref "S5") (pin "1") (pinfunction "1_1") (pintype "passive"))
      (node (ref "S5") (pin "2") (pinfunction "2_2") (pintype "passive"))
      (node (ref "U$5") (pin "4") (pinfunction "NRST_4") (pintype "bidirectional"))
      (node (ref "U2") (pin "7") (pinfunction "NRST_7") (pintype "bidirectional"))
    )
    (net (code "24") (name "I2C1_SCL") (class "Default")
      (node (ref "IC5") (pin "6") (pinfunction "SCL_6") (pintype "input"))
      (node (ref "JP4") (pin "2") (pinfunction "2_2") (pintype "passive"))
      (node (ref "R29") (pin "2") (pinfunction "2_2") (pintype "passive"))
      (node (ref "U2") (pin "42") (pinfunction "PB6_42") (pintype "bidirectional"))
    )
    (net (code "25") (name "I2C1_SDA") (class "Default")
      (node (ref "IC5") (pin "1") (pinfunction "SDA_1") (pintype "bidirectional"))
      (node (ref "JP4") (pin "3") (pinfunction "3_3") (pintype "passive"))
      (node (ref "R28") (pin "2") (pinfunction "2_2") (pintype "passive"))
      (node (ref "U2") (pin "43") (pinfunction "PB7_43") (pintype "bidirectional"))
    )
    (net (code "26") (name "LA1") (class "Default")
      (node (ref "J2") (pin "9") (pinfunction "G+_9") (pintype "bidirectional"))
      (node (ref "R17") (pin "1") (pinfunction "1_1") (pintype "passive"))
    )
    (net (code "27") (name "LA2") (class "Default")
      (node (ref "J3") (pin "9") (pinfunction "G+_9") (pintype "bidirectional"))
      (node (ref "R26") (pin "1") (pinfunction "1_1") (pintype "passive"))
    )
    (net (code "28") (name "LB1") (class "Default")
      (node (ref "J2") (pin "11") (pinfunction "Y+_11") (pintype "bidirectional"))
      (node (ref "R18") (pin "1") (pinfunction "1_1") (pintype "passive"))
    )
    (net (code "29") (name "LB2") (class "Default")
      (node (ref "J3") (pin "11") (pinfunction "Y+_11") (pintype "bidirectional"))
      (node (ref "R27") (pin "1") (pinfunction "1_1") (pintype "passive"))
    )
    (net (code "30") (name "LCD_D4") (class "Default")
      (node (ref "U$5") (pin "27") (pinfunction "PB4_27") (pintype "bidirectional"))
      (node (ref "U6") (pin "11") (pinfunction "DB4_11") (pintype "bidirectional"))
    )
    (net (code "31") (name "LCD_D5") (class "Default")
      (node (ref "U$5") (pin "28") (pinfunction "PB5_28") (pintype "bidirectional"))
      (node (ref "U6") (pin "12") (pinfunction "DB5_12") (pintype "bidirectional"))
    )
    (net (code "32") (name "LCD_D6") (class "Default")
      (node (ref "U$5") (pin "29") (pinfunction "PB6_29") (pintype "bidirectional"))
      (node (ref "U6") (pin "13") (pinfunction "DB6_13") (pintype "bidirectional"))
    )
    (net (code "33") (name "LCD_D7") (class "Default")
      (node (ref "U$5") (pin "30") (pinfunction "PB7_30") (pintype "bidirectional"))
      (node (ref "U6") (pin "14") (pinfunction "DB7_14") (pintype "bidirectional"))
    )
    (net (code "34") (name "LCD_E") (class "Default")
      (node (ref "U$5") (pin "26") (pinfunction "PB3_26") (pintype "bidirectional"))
      (node (ref "U6") (pin "6") (pinfunction "E_6") (pintype "input"))
    )
    (net (code "35") (name "LCD_RS") (class "Default")
      (node (ref "U$5") (pin "25") (pinfunction "PA15_25") (pintype "bidirectional"))
      (node (ref "U6") (pin "4") (pinfunction "RS_4") (pintype "input"))
    )
    (net (code "36") (name "Net-(BAT1-+)") (class "Default")
      (node (ref "BAT1") (pin "1") (pinfunction "+_1") (pintype "power_in"))
      (node (ref "D5") (pin "2") (pinfunction "A2_2") (pintype "passive"))
    )
    (net (code "37") (name "Net-(C26-+)") (class "Default")
      (node (ref "C26") (pin "A") (pinfunction "+_A") (pintype "passive"))
      (node (ref "U$1") (pin "43") (pinfunction "VCAP_43") (pintype "bidirectional"))
    )
    (net (code "38") (name "Net-(C40-+)") (class "Default")
      (node (ref "C40") (pin "A") (pinfunction "+_A") (pintype "passive"))
      (node (ref "U$3") (pin "43") (pinfunction "VCAP_43") (pintype "bidirectional"))
    )
    (net (code "39") (name "Net-(D8-PadA)") (class "Default")
      (node (ref "D8") (pin "A") (pinfunction "A_A") (pintype "passive"))
      (node (ref "U$2") (pin "P$1") (pinfunction "P$1_P$1") (pintype "bidirectional"))
    )
    (net (code "40") (name "Net-(JP3-PadD+)") (class "Default")
      (node (ref "JP3") (pin "D+") (pinfunction "D+_D+") (pintype "bidirectional"))
      (node (ref "R6") (pin "2") (pinfunction "2_2") (pintype "passive"))
    )
    (net (code "41") (name "Net-(JP3-PadD-)") (class "Default")
      (node (ref "JP3") (pin "D-") (pinfunction "D-_D-") (pintype "bidirectional"))
      (node (ref "R5") (pin "2") (pinfunction "2_2") (pintype "passive"))
    )
    (net (code "42") (name "Net-(K1-PadO)") (class "Default")
      (node (ref "K1") (pin "O") (pinfunction "O_O") (pintype "passive"))
      (node (ref "U$14") (pin "P$1") (pinfunction "P$1_P$1") (pintype "bidirectional"))
    )
    (net (code "43") (name "Net-(K1-PadP)") (class "Default")
      (node (ref "K1") (pin "P") (pinfunction "P_P") (pintype "passive"))
      (node (ref "U$14") (pin "P$2") (pinfunction "P$2_P$2") (pintype "bidirectional"))
    )
    (net (code "44") (name "Net-(K1-PadS)") (class "Default")
      (node (ref "K1") (pin "S") (pinfunction "S_S") (pintype "passive"))
      (node (ref "U$14") (pin "P$3") (pinfunction "P$3_P$3") (pintype "bidirectional"))
    )
    (net (code "45") (name "Net-(K2-PadO)") (class "Default")
      (node (ref "K2") (pin "O") (pinfunction "O_O") (pintype "passive"))
      (node (ref "U$15") (pin "P$1") (pinfunction "P$1_P$1") (pintype "bidirectional"))
    )
    (net (code "46") (name "Net-(K2-PadP)") (class "Default")
      (node (ref "K2") (pin "P") (pinfunction "P_P") (pintype "passive"))
      (node (ref "U$15") (pin "P$2") (pinfunction "P$2_P$2") (pintype "bidirectional"))
    )
    (net (code "47") (name "Net-(K2-PadS)") (class "Default")
      (node (ref "K2") (pin "S") (pinfunction "S_S") (pintype "passive"))
      (node (ref "U$15") (pin "P$3") (pinfunction "P$3_P$3") (pintype "bidirectional"))
    )
    (net (code "48") (name "Net-(K3-PadO)") (class "Default")
      (node (ref "K3") (pin "O") (pinfunction "O_O") (pintype "passive"))
      (node (ref "U$16") (pin "P$1") (pinfunction "P$1_P$1") (pintype "bidirectional"))
    )
    (net (code "49") (name "Net-(K3-PadP)") (class "Default")
      (node (ref "K3") (pin "P") (pinfunction "P_P") (pintype "passive"))
      (node (ref "U$16") (pin "P$2") (pinfunction "P$2_P$2") (pintype "bidirectional"))
    )
    (net (code "50") (name "Net-(K3-PadS)") (class "Default")
      (node (ref "K3") (pin "S") (pinfunction "S_S") (pintype "passive"))
      (node (ref "U$16") (pin "P$3") (pinfunction "P$3_P$3") (pintype "bidirectional"))
    )
    (net (code "51") (name "Net-(K4-PadO)") (class "Default")
      (node (ref "K4") (pin "O") (pinfunction "O_O") (pintype "passive"))
      (node (ref "U$17") (pin "P$1") (pinfunction "P$1_P$1") (pintype "bidirectional"))
    )
    (net (code "52") (name "Net-(K4-PadP)") (class "Default")
      (node (ref "K4") (pin "P") (pinfunction "P_P") (pintype "passive"))
      (node (ref "U$17") (pin "P$2") (pinfunction "P$2_P$2") (pintype "bidirectional"))
    )
    (net (code "53") (name "Net-(K4-PadS)") (class "Default")
      (node (ref "K4") (pin "S") (pinfunction "S_S") (pintype "passive"))
      (node (ref "U$17") (pin "P$3") (pinfunction "P$3_P$3") (pintype "bidirectional"))
    )
    (net (code "54") (name "Net-(L4-Pad1)") (class "Default")
      (node (ref "L4") (pin "1") (pinfunction "1_1") (pintype "passive"))
      (node (ref "R12") (pin "2") (pinfunction "2_2") (pintype "passive"))
      (node (ref "R13") (pin "2") (pinfunction "2_2") (pintype "passive"))
      (node (ref "R16") (pin "2") (pinfunction "2_2") (pintype "passive"))
    )
    (net (code "55") (name "Net-(L5-Pad1)") (class "Default")
      (node (ref "L5") (pin "1") (pinfunction "1_1") (pintype "passive"))
      (node (ref "R21") (pin "2") (pinfunction "2_2") (pintype "passive"))
      (node (ref "R22") (pin "2") (pinfunction "2_2") (pintype "passive"))
      (node (ref "R25") (pin "2") (pinfunction "2_2") (pintype "passive"))
    )
    (net (code "56") (name "Net-(LED1-PadA)") (class "Default")
      (node (ref "LED1") (pin "A") (pinfunction "A_A") (pintype "passive"))
      (node (ref "R31") (pin "2") (pinfunction "2_2") (pintype "passive"))
    )
    (net (code "57") (name "Net-(LED2-PadA)") (class "Default")
      (node (ref "LED2") (pin "A") (pinfunction "A_A") (pintype "passive"))
      (node (ref "R33") (pin "2") (pinfunction "2_2") (pintype "passive"))
    )
    (net (code "58") (name "Net-(LED3-PadA)") (class "Default")
      (node (ref "LED3") (pin "A") (pinfunction "A_A") (pintype "passive"))
      (node (ref "R34") (pin "2") (pinfunction "2_2") (pintype "passive"))
    )
    (net (code "59") (name "Net-(LED4-PadA)") (class "Default")
      (node (ref "LED4") (pin "A") (pinfunction "A_A") (pintype "passive"))
      (node (ref "R35") (pin "2") (pinfunction "2_2") (pintype "passive"))
    )
    (net (code "60") (name "Net-(LED5-PadA)") (class "Default")
      (node (ref "LED5") (pin "A") (pinfunction "A_A") (pintype "passive"))
      (node (ref "R36") (pin "2") (pinfunction "2_2") (pintype "passive"))
    )
    (net (code "61") (name "Net-(LED6-PadA)") (class "Default")
      (node (ref "LED6") (pin "A") (pinfunction "A_A") (pintype "passive"))
      (node (ref "R38") (pin "2") (pinfunction "2_2") (pintype "passive"))
    )
    (net (code "62") (name "Net-(LED7-PadA)") (class "Default")
      (node (ref "LED7") (pin "A") (pinfunction "A_A") (pintype "passive"))
      (node (ref "R37") (pin "2") (pinfunction "2_2") (pintype "passive"))
    )
    (net (code "63") (name "Net-(LED8-PadA)") (class "Default")
      (node (ref "LED8") (pin "A") (pinfunction "A_A") (pintype "passive"))
      (node (ref "R32") (pin "2") (pinfunction "2_2") (pintype "passive"))
    )
    (net (code "64") (name "Net-(LED9-PadA)") (class "Default")
      (node (ref "LED9") (pin "A") (pinfunction "A_A") (pintype "passive"))
      (node (ref "R39") (pin "2") (pinfunction "2_2") (pintype "passive"))
    )
    (net (code "65") (name "Net-(LED10-PadA)") (class "Default")
      (node (ref "LED10") (pin "A") (pinfunction "A_A") (pintype "passive"))
      (node (ref "R40") (pin "2") (pinfunction "2_2") (pintype "passive"))
    )
    (net (code "66") (name "Net-(LED11-PadA)") (class "Default")
      (node (ref "LED11") (pin "A") (pinfunction "A_A") (pintype "passive"))
      (node (ref "R41") (pin "2") (pinfunction "2_2") (pintype "passive"))
    )
    (net (code "67") (name "Net-(LED12-PadA)") (class "Default")
      (node (ref "LED12") (pin "A") (pinfunction "A_A") (pintype "passive"))
      (node (ref "R42") (pin "2") (pinfunction "2_2") (pintype "passive"))
    )
    (net (code "68") (name "Net-(LED13-PadA)") (class "Default")
      (node (ref "LED13") (pin "A") (pinfunction "A_A") (pintype "passive"))
      (node (ref "R44") (pin "2") (pinfunction "2_2") (pintype "passive"))
    )
    (net (code "69") (name "Net-(R30-WIPER)") (class "Default")
      (node (ref "R30") (pin "2") (pinfunction "WIPER_2") (pintype "passive"))
      (node (ref "U6") (pin "3") (pinfunction "VO_3") (pintype "bidirectional"))
    )
    (net (code "70") (name "Net-(T1-D)") (class "Default")
      (node (ref "D7") (pin "A") (pinfunction "A_A") (pintype "passive"))
      (node (ref "K1") (pin "2") (pinfunction "2_2") (pintype "passive"))
      (node (ref "T1") (pin "3") (pinfunction "D_3") (pintype "passive"))
    )
    (net (code "71") (name "Net-(T2-D)") (class "Default")
      (node (ref "D6") (pin "A") (pinfunction "A_A") (pintype "passive"))
      (node (ref "K2") (pin "2") (pinfunction "2_2") (pintype "passive"))
      (node (ref "T2") (pin "3") (pinfunction "D_3") (pintype "passive"))
    )
    (net (code "72") (name "Net-(T3-D)") (class "Default")
      (node (ref "D2") (pin "A") (pinfunction "A_A") (pintype "passive"))
      (node (ref "K3") (pin "2") (pinfunction "2_2") (pintype "passive"))
      (node (ref "T3") (pin "3") (pinfunction "D_3") (pintype "passive"))
    )
    (net (code "73") (name "Net-(T4-D)") (class "Default")
      (node (ref "D3") (pin "A") (pinfunction "A_A") (pintype "passive"))
      (node (ref "K4") (pin "2") (pinfunction "2_2") (pintype "passive"))
      (node (ref "T4") (pin "3") (pinfunction "D_3") (pintype "passive"))
    )
    (net (code "74") (name "Net-(U$1-LEDA)") (class "Default")
      (node (ref "R17") (pin "2") (pinfunction "2_2") (pintype "passive"))
      (node (ref "U$1") (pin "10") (pinfunction "LEDA_10") (pintype "bidirectional"))
    )
    (net (code "75") (name "Net-(U$1-LEDB)") (class "Default")
      (node (ref "R18") (pin "2") (pinfunction "2_2") (pintype "passive"))
      (node (ref "U$1") (pin "9") (pinfunction "LEDB_9") (pintype "bidirectional"))
    )
    (net (code "76") (name "Net-(U$1-OSC1)") (class "Default")
      (node (ref "C24") (pin "1") (pinfunction "1_1") (pintype "passive"))
      (node (ref "U$1") (pin "3") (pinfunction "OSC1_3") (pintype "bidirectional"))
      (node (ref "Y3") (pin "P$1") (pinfunction "1_P$1") (pintype "passive"))
    )
    (net (code "77") (name "Net-(U$1-OSC2)") (class "Default")
      (node (ref "C25") (pin "1") (pinfunction "1_1") (pintype "passive"))
      (node (ref "U$1") (pin "2") (pinfunction "OSC2_2") (pintype "bidirectional"))
      (node (ref "Y3") (pin "P$2") (pinfunction "2_P$2") (pintype "passive"))
    )
    (net (code "78") (name "Net-(U$1-RBIAS)") (class "Default")
      (node (ref "R10") (pin "2") (pinfunction "2_2") (pintype "passive"))
      (node (ref "U$1") (pin "11") (pinfunction "RBIAS_11") (pintype "bidirectional"))
    )
    (net (code "79") (name "Net-(U$1-TPIN+)") (class "Default")
      (node (ref "C30") (pin "1") (pinfunction "1_1") (pintype "passive"))
      (node (ref "R15") (pin "2") (pinfunction "2_2") (pintype "passive"))
      (node (ref "U$1") (pin "16") (pinfunction "TPIN+_16") (pintype "bidirectional"))
    )
    (net (code "80") (name "Net-(U$1-TPIN-)") (class "Default")
      (node (ref "C31") (pin "1") (pinfunction "1_1") (pintype "passive"))
      (node (ref "R14") (pin "2") (pinfunction "2_2") (pintype "passive"))
      (node (ref "U$1") (pin "17") (pinfunction "TPIN-_17") (pintype "bidirectional"))
    )
    (net (code "81") (name "Net-(U$1-~{INT{slash}SPISEL})") (class "Default")
      (node (ref "R11") (pin "1") (pinfunction "1_1") (pintype "passive"))
      (node (ref "U$1") (pin "24") (pinfunction "~{INT/SPISEL}_24") (pintype "bidirectional"))
    )
    (net (code "82") (name "Net-(U$3-LEDA)") (class "Default")
      (node (ref "R26") (pin "2") (pinfunction "2_2") (pintype "passive"))
      (node (ref "U$3") (pin "10") (pinfunction "LEDA_10") (pintype "bidirectional"))
    )
    (net (code "83") (name "Net-(U$3-LEDB)") (class "Default")
      (node (ref "R27") (pin "2") (pinfunction "2_2") (pintype "passive"))
      (node (ref "U$3") (pin "9") (pinfunction "LEDB_9") (pintype "bidirectional"))
    )
    (net (code "84") (name "Net-(U$3-OSC1)") (class "Default")
      (node (ref "C36") (pin "1") (pinfunction "1_1") (pintype "passive"))
      (node (ref "U$3") (pin "3") (pinfunction "OSC1_3") (pintype "bidirectional"))
      (node (ref "Y4") (pin "P$1") (pinfunction "1_P$1") (pintype "passive"))
    )
    (net (code "85") (name "Net-(U$3-OSC2)") (class "Default")
      (node (ref "C37") (pin "1") (pinfunction "1_1") (pintype "passive"))
      (node (ref "U$3") (pin "2") (pinfunction "OSC2_2") (pintype "bidirectional"))
      (node (ref "Y4") (pin "P$2") (pinfunction "2_P$2") (pintype "passive"))
    )
    (net (code "86") (name "Net-(U$3-RBIAS)") (class "Default")
      (node (ref "R19") (pin "2") (pinfunction "2_2") (pintype "passive"))
      (node (ref "U$3") (pin "11") (pinfunction "RBIAS_11") (pintype "bidirectional"))
    )
    (net (code "87") (name "Net-(U$3-TPIN+)") (class "Default")
      (node (ref "C42") (pin "1") (pinfunction "1_1") (pintype "passive"))
      (node (ref "R24") (pin "2") (pinfunction "2_2") (pintype "passive"))
      (node (ref "U$3") (pin "16") (pinfunction "TPIN+_16") (pintype "bidirectional"))
    )
    (net (code "88") (name "Net-(U$3-TPIN-)") (class "Default")
      (node (ref "C43") (pin "1") (pinfunction "1_1") (pintype "passive"))
      (node (ref "R23") (pin "2") (pinfunction "2_2") (pintype "passive"))
      (node (ref "U$3") (pin "17") (pinfunction "TPIN-_17") (pintype "bidirectional"))
    )
    (net (code "89") (name "Net-(U$3-~{INT{slash}SPISEL})") (class "Default")
      (node (ref "R20") (pin "1") (pinfunction "1_1") (pintype "passive"))
      (node (ref "U$3") (pin "24") (pinfunction "~{INT/SPISEL}_24") (pintype "bidirectional"))
    )
    (net (code "90") (name "Net-(U$4-S)") (class "Default")
      (node (ref "JP12") (pin "8") (pinfunction "8_8") (pintype "passive"))
      (node (ref "R43") (pin "1") (pinfunction "1_1") (pintype "passive"))
      (node (ref "U$4") (pin "P$2") (pinfunction "S_P$2") (pintype "bidirectional"))
    )
    (net (code "91") (name "Net-(U$5-BOOT0)") (class "Default")
      (node (ref "R48") (pin "1") (pinfunction "1_1") (pintype "passive"))
      (node (ref "U$5") (pin "31") (pinfunction "BOOT0_31") (pintype "bidirectional"))
    )
    (net (code "92") (name "Net-(U$5-PA13{slash}SWDIO)") (class "Default")
      (node (ref "JP11") (pin "3") (pinfunction "3_3") (pintype "passive"))
      (node (ref "U$5") (pin "23") (pinfunction "PA13/SWDIO_23") (pintype "bidirectional"))
    )
    (net (code "93") (name "Net-(U$5-PA14{slash}SWCLK)") (class "Default")
      (node (ref "JP11") (pin "2") (pinfunction "2_2") (pintype "passive"))
      (node (ref "U$5") (pin "24") (pinfunction "PA14/SWCLK_24") (pintype "bidirectional"))
    )
    (net (code "94") (name "Net-(U1-COMP)") (class "Default")
      (node (ref "R2") (pin "1") (pinfunction "1_1") (pintype "passive"))
      (node (ref "R3") (pin "1") (pinfunction "1_1") (pintype "passive"))
      (node (ref "U1") (pin "5") (pinfunction "COMP_5") (pintype "bidirectional"))
    )
    (net (code "95") (name "Net-(U1-SWE)") (class "Default")
      (node (ref "D1") (pin "C") (pinfunction "C_C") (pintype "passive"))
      (node (ref "L1") (pin "1") (pinfunction "1_1") (pintype "passive"))
      (node (ref "U1") (pin "2") (pinfunction "SWE_2") (pintype "bidirectional"))
    )
    (net (code "96") (name "Net-(U1-TC)") (class "Default")
      (node (ref "C3") (pin "1") (pinfunction "1_1") (pintype "passive"))
      (node (ref "U1") (pin "3") (pinfunction "TC_3") (pintype "bidirectional"))
    )
    (net (code "97") (name "Net-(U2-BOOT0)") (class "Default")
      (node (ref "R47") (pin "2") (pinfunction "2_2") (pintype "passive"))
      (node (ref "U2") (pin "44") (pinfunction "BOOT0_44") (pintype "bidirectional"))
    )
    (net (code "98") (name "Net-(U2-PC14-OSC32_IN)") (class "Default")
      (node (ref "C12") (pin "1") (pinfunction "1_1") (pintype "passive"))
      (node (ref "U2") (pin "3") (pinfunction "PC14-OSC32_IN_3") (pintype "bidirectional"))
      (node (ref "Y1") (pin "1") (pinfunction "1_1") (pintype "passive"))
    )
    (net (code "99") (name "Net-(U2-PC15-OSC32_OUT)") (class "Default")
      (node (ref "C11") (pin "1") (pinfunction "1_1") (pintype "passive"))
      (node (ref "U2") (pin "4") (pinfunction "PC15-OSC32_OUT_4") (pintype "bidirectional"))
      (node (ref "Y1") (pin "4") (pinfunction "2_4") (pintype "passive"))
    )
    (net (code "100") (name "Net-(U2-PD0-OSC_IN)") (class "Default")
      (node (ref "C13") (pin "1") (pinfunction "1_1") (pintype "passive"))
      (node (ref "R46") (pin "2") (pinfunction "2_2") (pintype "passive"))
      (node (ref "U2") (pin "5") (pinfunction "PD0-OSC_IN_5") (pintype "bidirectional"))
      (node (ref "Y2") (pin "2") (pinfunction "2_2") (pintype "passive"))
    )
    (net (code "101") (name "Net-(U2-PD1-OSC_OUT)") (class "Default")
      (node (ref "C14") (pin "1") (pinfunction "1_1") (pintype "passive"))
      (node (ref "R46") (pin "1") (pinfunction "1_1") (pintype "passive"))
      (node (ref "U2") (pin "6") (pinfunction "PD1-OSC_OUT_6") (pintype "bidirectional"))
      (node (ref "Y2") (pin "1") (pinfunction "1_1") (pintype "passive"))
    )
    (net (code "102") (name "Net-(U3-COMP)") (class "Default")
      (node (ref "R8") (pin "1") (pinfunction "1_1") (pintype "passive"))
      (node (ref "R9") (pin "1") (pinfunction "1_1") (pintype "passive"))
      (node (ref "U3") (pin "5") (pinfunction "COMP_5") (pintype "bidirectional"))
    )
    (net (code "103") (name "Net-(U3-SWE)") (class "Default")
      (node (ref "D4") (pin "C") (pinfunction "C_C") (pintype "passive"))
      (node (ref "L3") (pin "1") (pinfunction "1_1") (pintype "passive"))
      (node (ref "U3") (pin "2") (pinfunction "SWE_2") (pintype "bidirectional"))
    )
    (net (code "104") (name "Net-(U3-TC)") (class "Default")
      (node (ref "C17") (pin "1") (pinfunction "1_1") (pintype "passive"))
      (node (ref "U3") (pin "3") (pinfunction "TC_3") (pintype "bidirectional"))
    )
    (net (code "105") (name "Net-(U4-C1+)") (class "Default")
      (node (ref "C18") (pin "1") (pinfunction "1_1") (pintype "passive"))
      (node (ref "U4") (pin "1") (pinfunction "C1+_1") (pintype "input"))
    )
    (net (code "106") (name "Net-(U4-C1-)") (class "Default")
      (node (ref "C18") (pin "2") (pinfunction "2_2") (pintype "passive"))
      (node (ref "U4") (pin "3") (pinfunction "C1-_3") (pintype "input"))
    )
    (net (code "107") (name "Net-(U4-C2+)") (class "Default")
      (node (ref "C19") (pin "2") (pinfunction "2_2") (pintype "passive"))
      (node (ref "U4") (pin "4") (pinfunction "C2+_4") (pintype "input"))
    )
    (net (code "108") (name "Net-(U4-C2-)") (class "Default")
      (node (ref "C19") (pin "1") (pinfunction "1_1") (pintype "passive"))
      (node (ref "U4") (pin "5") (pinfunction "C2-_5") (pintype "input"))
    )
    (net (code "109") (name "Net-(U4-V+)") (class "Default")
      (node (ref "C21") (pin "2") (pinfunction "2_2") (pintype "passive"))
      (node (ref "U4") (pin "2") (pinfunction "V+_2") (pintype "input"))
    )
    (net (code "110") (name "Net-(U4-V-)") (class "Default")
      (node (ref "C20") (pin "2") (pinfunction "2_2") (pintype "passive"))
      (node (ref "U4") (pin "6") (pinfunction "V-_6") (pintype "input"))
    )
    (net (code "111") (name "Net-(U4-VCC)") (class "Default")
      (node (ref "C22") (pin "2") (pinfunction "2_2") (pintype "passive"))
      (node (ref "U4") (pin "16") (pinfunction "VCC_16") (pintype "power_in"))
    )
    (net (code "112") (name "RX1+") (class "Default")
      (node (ref "C30") (pin "2") (pinfunction "2_2") (pintype "passive"))
      (node (ref "J2") (pin "4") (pinfunction "RD+_4") (pintype "bidirectional"))
    )
    (net (code "113") (name "RX1-") (class "Default")
      (node (ref "C31") (pin "2") (pinfunction "2_2") (pintype "passive"))
      (node (ref "J2") (pin "6") (pinfunction "RD-_6") (pintype "bidirectional"))
    )
    (net (code "114") (name "RX1_CT") (class "Default")
      (node (ref "C32") (pin "2") (pinfunction "2_2") (pintype "passive"))
      (node (ref "J2") (pin "5") (pinfunction "RXCT_5") (pintype "bidirectional"))
      (node (ref "R14") (pin "1") (pinfunction "1_1") (pintype "passive"))
      (node (ref "R15") (pin "1") (pinfunction "1_1") (pintype "passive"))
    )
    (net (code "115") (name "RX2+") (class "Default")
      (node (ref "C42") (pin "2") (pinfunction "2_2") (pintype "passive"))
      (node (ref "J3") (pin "4") (pinfunction "RD+_4") (pintype "bidirectional"))
    )
    (net (code "116") (name "RX2-") (class "Default")
      (node (ref "C43") (pin "2") (pinfunction "2_2") (pintype "passive"))
      (node (ref "J3") (pin "6") (pinfunction "RD-_6") (pintype "bidirectional"))
    )
    (net (code "117") (name "RX2_CT") (class "Default")
      (node (ref "C44") (pin "2") (pinfunction "2_2") (pintype "passive"))
      (node (ref "J3") (pin "5") (pinfunction "RXCT_5") (pintype "bidirectional"))
      (node (ref "R23") (pin "1") (pinfunction "1_1") (pintype "passive"))
      (node (ref "R24") (pin "1") (pinfunction "1_1") (pintype "passive"))
    )
    (net (code "118") (name "SPI1_MISO") (class "Default")
      (node (ref "JP1") (pin "2") (pinfunction "2_2") (pintype "passive"))
      (node (ref "U$1") (pin "35") (pinfunction "SO/WR/EN_35") (pintype "bidirectional"))
      (node (ref "U2") (pin "16") (pinfunction "PA6_16") (pintype "bidirectional"))
    )
    (net (code "119") (name "SPI1_MOSI") (class "Default")
      (node (ref "JP1") (pin "3") (pinfunction "3_3") (pintype "passive"))
      (node (ref "U$1") (pin "36") (pinfunction "SI/RD/~{RW}_36") (pintype "bidirectional"))
      (node (ref "U2") (pin "17") (pinfunction "PA7_17") (pintype "bidirectional"))
    )
    (net (code "120") (name "SPI1_SCK") (class "Default")
      (node (ref "JP1") (pin "4") (pinfunction "4_4") (pintype "passive"))
      (node (ref "U$1") (pin "37") (pinfunction "SCK/AL_37") (pintype "bidirectional"))
      (node (ref "U2") (pin "15") (pinfunction "PA5_15") (pintype "bidirectional"))
    )
    (net (code "121") (name "SPI1_SS1_ETH1") (class "Default")
      (node (ref "JP1") (pin "1") (pinfunction "1_1") (pintype "passive"))
      (node (ref "U$1") (pin "34") (pinfunction "CS/~{CS}_34") (pintype "bidirectional"))
      (node (ref "U2") (pin "18") (pinfunction "PB0_18") (pintype "bidirectional"))
    )
    (net (code "122") (name "SPI2_MISO") (class "Default")
      (node (ref "JP5") (pin "6") (pinfunction "6_6") (pintype "passive"))
      (node (ref "U$3") (pin "35") (pinfunction "SO/WR/EN_35") (pintype "bidirectional"))
      (node (ref "U2") (pin "28") (pinfunction "PB15_28") (pintype "bidirectional"))
      (node (ref "U5") (pin "2") (pinfunction "SO_(IO1)_2") (pintype "output"))
    )
    (net (code "123") (name "SPI2_MOSI") (class "Default")
      (node (ref "JP5") (pin "5") (pinfunction "5_5") (pintype "passive"))
      (node (ref "U$3") (pin "36") (pinfunction "SI/RD/~{RW}_36") (pintype "bidirectional"))
      (node (ref "U2") (pin "27") (pinfunction "PB14_27") (pintype "bidirectional"))
      (node (ref "U5") (pin "5") (pinfunction "SI_(IO0)_5") (pintype "bidirectional"))
    )
    (net (code "124") (name "SPI2_SCK") (class "Default")
      (node (ref "JP5") (pin "7") (pinfunction "7_7") (pintype "passive"))
      (node (ref "U$3") (pin "37") (pinfunction "SCK/AL_37") (pintype "bidirectional"))
      (node (ref "U2") (pin "26") (pinfunction "PB13_26") (pintype "bidirectional"))
      (node (ref "U5") (pin "6") (pinfunction "CLK_6") (pintype "input"))
    )
    (net (code "125") (name "SPI2_SS1_ETH2") (class "Default")
      (node (ref "JP5") (pin "3") (pinfunction "3_3") (pintype "passive"))
      (node (ref "U$3") (pin "34") (pinfunction "CS/~{CS}_34") (pintype "bidirectional"))
      (node (ref "U2") (pin "29") (pinfunction "PA8_29") (pintype "bidirectional"))
    )
    (net (code "126") (name "SPI2_SS2_FLASH") (class "Default")
      (node (ref "JP5") (pin "4") (pinfunction "4_4") (pintype "passive"))
      (node (ref "U2") (pin "25") (pinfunction "PB12_25") (pintype "bidirectional"))
      (node (ref "U5") (pin "1") (pinfunction "CS_1") (pintype "input"))
    )
    (net (code "127") (name "SW0") (class "Default")
      (node (ref "S1") (pin "1") (pinfunction "1_1") (pintype "passive"))
      (node (ref "S1") (pin "2") (pinfunction "2_2") (pintype "passive"))
      (node (ref "U$5") (pin "2") (pinfunction "PF0/OSC_IN_2") (pintype "bidirectional"))
    )
    (net (code "128") (name "SW1") (class "Default")
      (node (ref "S2") (pin "1") (pinfunction "1_1") (pintype "passive"))
      (node (ref "S2") (pin "2") (pinfunction "2_2") (pintype "passive"))
      (node (ref "U$5") (pin "3") (pinfunction "PF1/OSC_OUT_3") (pintype "bidirectional"))
    )
    (net (code "129") (name "SW2") (class "Default")
      (node (ref "S3") (pin "1") (pinfunction "1_1") (pintype "passive"))
      (node (ref "S3") (pin "2") (pinfunction "2_2") (pintype "passive"))
      (node (ref "U2") (pin "14") (pinfunction "PA4_14") (pintype "bidirectional"))
    )
    (net (code "130") (name "SW3") (class "Default")
      (node (ref "S4") (pin "1") (pinfunction "1_1") (pintype "passive"))
      (node (ref "S4") (pin "2") (pinfunction "2_2") (pintype "passive"))
      (node (ref "U2") (pin "19") (pinfunction "PB1_19") (pintype "bidirectional"))
    )
    (net (code "131") (name "SWDCLK") (class "Default")
      (node (ref "JP2") (pin "2") (pinfunction "2_2") (pintype "passive"))
      (node (ref "U2") (pin "37") (pinfunction "PA14_37") (pintype "bidirectional"))
    )
    (net (code "132") (name "SWDIO") (class "Default")
      (node (ref "JP2") (pin "3") (pinfunction "3_3") (pintype "passive"))
      (node (ref "U2") (pin "34") (pinfunction "PA13_34") (pintype "bidirectional"))
    )
    (net (code "133") (name "TX1+") (class "Default")
      (node (ref "J2") (pin "1") (pinfunction "TD+_1") (pintype "bidirectional"))
      (node (ref "R12") (pin "1") (pinfunction "1_1") (pintype "passive"))
      (node (ref "U$1") (pin "20") (pinfunction "TPOUT+_20") (pintype "bidirectional"))
    )
    (net (code "134") (name "TX1-") (class "Default")
      (node (ref "J2") (pin "3") (pinfunction "TD-_3") (pintype "bidirectional"))
      (node (ref "R13") (pin "1") (pinfunction "1_1") (pintype "passive"))
      (node (ref "U$1") (pin "21") (pinfunction "TPOUT-_21") (pintype "bidirectional"))
    )
    (net (code "135") (name "TX1_CT") (class "Default")
      (node (ref "C29") (pin "1") (pinfunction "1_1") (pintype "passive"))
      (node (ref "J2") (pin "2") (pinfunction "TXCT_2") (pintype "bidirectional"))
      (node (ref "R16") (pin "1") (pinfunction "1_1") (pintype "passive"))
    )
    (net (code "136") (name "TX2+") (class "Default")
      (node (ref "J3") (pin "1") (pinfunction "TD+_1") (pintype "bidirectional"))
      (node (ref "R21") (pin "1") (pinfunction "1_1") (pintype "passive"))
      (node (ref "U$3") (pin "20") (pinfunction "TPOUT+_20") (pintype "bidirectional"))
    )
    (net (code "137") (name "TX2-") (class "Default")
      (node (ref "J3") (pin "3") (pinfunction "TD-_3") (pintype "bidirectional"))
      (node (ref "R22") (pin "1") (pinfunction "1_1") (pintype "passive"))
      (node (ref "U$3") (pin "21") (pinfunction "TPOUT-_21") (pintype "bidirectional"))
    )
    (net (code "138") (name "TX2_CT") (class "Default")
      (node (ref "C41") (pin "1") (pinfunction "1_1") (pintype "passive"))
      (node (ref "J3") (pin "2") (pinfunction "TXCT_2") (pintype "bidirectional"))
      (node (ref "R25") (pin "1") (pinfunction "1_1") (pintype "passive"))
    )
    (net (code "139") (name "UART_RX1") (class "Default")
      (node (ref "JP6") (pin "1") (pinfunction "1_1") (pintype "passive"))
      (node (ref "U2") (pin "22") (pinfunction "PB11_22") (pintype "bidirectional"))
    )
    (net (code "140") (name "UART_RX2") (class "Default")
      (node (ref "JP7") (pin "2") (pinfunction "2_2") (pintype "passive"))
      (node (ref "U2") (pin "31") (pinfunction "PA10_31") (pintype "bidirectional"))
      (node (ref "U4") (pin "12") (pinfunction "R1OUT_12") (pintype "output"))
    )
    (net (code "141") (name "UART_TX1") (class "Default")
      (node (ref "JP6") (pin "2") (pinfunction "2_2") (pintype "passive"))
      (node (ref "U2") (pin "21") (pinfunction "PB10_21") (pintype "bidirectional"))
    )
    (net (code "142") (name "UART_TX2") (class "Default")
      (node (ref "JP7") (pin "3") (pinfunction "3_3") (pintype "passive"))
      (node (ref "U2") (pin "30") (pinfunction "PA9_30") (pintype "bidirectional"))
      (node (ref "U4") (pin "11") (pinfunction "T1IN_11") (pintype "input"))
    )
    (net (code "143") (name "USB_D+") (class "Default")
      (node (ref "R45") (pin "1") (pinfunction "1_1") (pintype "passive"))
      (node (ref "R6") (pin "1") (pinfunction "1_1") (pintype "passive"))
      (node (ref "U2") (pin "33") (pinfunction "PA12_33") (pintype "bidirectional"))
    )
    (net (code "144") (name "USB_D-") (class "Default")
      (node (ref "R5") (pin "1") (pinfunction "1_1") (pintype "passive"))
      (node (ref "U2") (pin "32") (pinfunction "PA11_32") (pintype "power_in"))
    )
    (net (code "145") (name "VBAT") (class "Default")
      (node (ref "D5") (pin "3") (pinfunction "C_3") (pintype "passive"))
      (node (ref "U2") (pin "1") (pinfunction "VBAT_1") (pintype "input"))
    )
    (net (code "146") (name "VIN") (class "Default")
      (node (ref "C15") (pin "1") (pinfunction "+_1") (pintype "passive"))
      (node (ref "D8") (pin "C") (pinfunction "C_C") (pintype "passive"))
      (node (ref "R7") (pin "2") (pinfunction "2_2") (pintype "passive"))
      (node (ref "U3") (pin "6") (pinfunction "VCC_6") (pintype "bidirectional"))
    )
    (net (code "147") (name "VIN2") (class "Default")
      (node (ref "R7") (pin "1") (pinfunction "1_1") (pintype "passive"))
      (node (ref "U3") (pin "1") (pinfunction "SWC_1") (pintype "bidirectional"))
      (node (ref "U3") (pin "7") (pinfunction "SEN_7") (pintype "bidirectional"))
      (node (ref "U3") (pin "8") (pinfunction "DVR_8") (pintype "bidirectional"))
    )
    (net (code "148") (name "VIN3") (class "Default")
      (node (ref "R1") (pin "1") (pinfunction "1_1") (pintype "passive"))
      (node (ref "U1") (pin "1") (pinfunction "SWC_1") (pintype "bidirectional"))
      (node (ref "U1") (pin "7") (pinfunction "SEN_7") (pintype "bidirectional"))
      (node (ref "U1") (pin "8") (pinfunction "DVR_8") (pintype "bidirectional"))
    )
    (net (code "149") (name "unconnected-(IC5-DNC-Pad3)") (class "Default")
      (node (ref "IC5") (pin "3") (pinfunction "DNC_3") (pintype "no_connect"))
    )
    (net (code "150") (name "unconnected-(IC5-DNC-Pad4)") (class "Default")
      (node (ref "IC5") (pin "4") (pinfunction "DNC_4") (pintype "no_connect"))
    )
    (net (code "151") (name "unconnected-(J2-NC-Pad7)") (class "Default")
      (node (ref "J2") (pin "7") (pinfunction "NC_7") (pintype "bidirectional"))
    )
    (net (code "152") (name "unconnected-(J3-NC-Pad7)") (class "Default")
      (node (ref "J3") (pin "7") (pinfunction "NC_7") (pintype "bidirectional"))
    )
    (net (code "153") (name "unconnected-(JP3-PadVBUS)") (class "Default")
      (node (ref "JP3") (pin "VBUS") (pinfunction "VBUS_VBUS") (pintype "bidirectional"))
    )
    (net (code "154") (name "unconnected-(JP12-Pad4)") (class "Default")
      (node (ref "JP12") (pin "4") (pinfunction "4_4") (pintype "passive"))
    )
    (net (code "155") (name "unconnected-(JP12-Pad6)") (class "Default")
      (node (ref "JP12") (pin "6") (pinfunction "6_6") (pintype "passive"))
    )
    (net (code "156") (name "unconnected-(JP12-Pad9)") (class "Default")
      (node (ref "JP12") (pin "9") (pinfunction "9_9") (pintype "passive"))
    )
    (net (code "157") (name "unconnected-(JP12-Pad10)") (class "Default")
      (node (ref "JP12") (pin "10") (pinfunction "10_10") (pintype "passive"))
    )
    (net (code "158") (name "unconnected-(U$1-AD0-Pad38)") (class "Default")
      (node (ref "U$1") (pin "38") (pinfunction "AD0_38") (pintype "bidirectional"))
    )
    (net (code "159") (name "unconnected-(U$1-AD1-Pad39)") (class "Default")
      (node (ref "U$1") (pin "39") (pinfunction "AD1_39") (pintype "bidirectional"))
    )
    (net (code "160") (name "unconnected-(U$1-AD2-Pad40)") (class "Default")
      (node (ref "U$1") (pin "40") (pinfunction "AD2_40") (pintype "bidirectional"))
    )
    (net (code "161") (name "unconnected-(U$1-AD3-Pad41)") (class "Default")
      (node (ref "U$1") (pin "41") (pinfunction "AD3_41") (pintype "bidirectional"))
    )
    (net (code "162") (name "unconnected-(U$1-AD4-Pad5)") (class "Default")
      (node (ref "U$1") (pin "5") (pinfunction "AD4_5") (pintype "bidirectional"))
    )
    (net (code "163") (name "unconnected-(U$1-AD5-Pad6)") (class "Default")
      (node (ref "U$1") (pin "6") (pinfunction "AD5_6") (pintype "bidirectional"))
    )
    (net (code "164") (name "unconnected-(U$1-AD6-Pad7)") (class "Default")
      (node (ref "U$1") (pin "7") (pinfunction "AD6_7") (pintype "bidirectional"))
    )
    (net (code "165") (name "unconnected-(U$1-AD7-Pad8)") (class "Default")
      (node (ref "U$1") (pin "8") (pinfunction "AD7_8") (pintype "bidirectional"))
    )
    (net (code "166") (name "unconnected-(U$1-AD8-Pad25)") (class "Default")
      (node (ref "U$1") (pin "25") (pinfunction "AD8_25") (pintype "bidirectional"))
    )
    (net (code "167") (name "unconnected-(U$1-AD9-Pad26)") (class "Default")
      (node (ref "U$1") (pin "26") (pinfunction "AD9_26") (pintype "bidirectional"))
    )
    (net (code "168") (name "unconnected-(U$1-AD10-Pad27)") (class "Default")
      (node (ref "U$1") (pin "27") (pinfunction "AD10_27") (pintype "bidirectional"))
    )
    (net (code "169") (name "unconnected-(U$1-AD11-Pad28)") (class "Default")
      (node (ref "U$1") (pin "28") (pinfunction "AD11_28") (pintype "bidirectional"))
    )
    (net (code "170") (name "unconnected-(U$1-AD12-Pad29)") (class "Default")
      (node (ref "U$1") (pin "29") (pinfunction "AD12_29") (pintype "bidirectional"))
    )
    (net (code "171") (name "unconnected-(U$1-AD13-Pad30)") (class "Default")
      (node (ref "U$1") (pin "30") (pinfunction "AD13_30") (pintype "bidirectional"))
    )
    (net (code "172") (name "unconnected-(U$1-AD14-Pad31)") (class "Default")
      (node (ref "U$1") (pin "31") (pinfunction "AD14_31") (pintype "bidirectional"))
    )
    (net (code "173") (name "unconnected-(U$1-CLKOUT-Pad23)") (class "Default")
      (node (ref "U$1") (pin "23") (pinfunction "CLKOUT_23") (pintype "bidirectional"))
    )
    (net (code "174") (name "unconnected-(U$1-PSPCFG0-Pad32)") (class "Default")
      (node (ref "U$1") (pin "32") (pinfunction "PSPCFG0_32") (pintype "bidirectional"))
    )
    (net (code "175") (name "unconnected-(U$3-AD0-Pad38)") (class "Default")
      (node (ref "U$3") (pin "38") (pinfunction "AD0_38") (pintype "bidirectional"))
    )
    (net (code "176") (name "unconnected-(U$3-AD1-Pad39)") (class "Default")
      (node (ref "U$3") (pin "39") (pinfunction "AD1_39") (pintype "bidirectional"))
    )
    (net (code "177") (name "unconnected-(U$3-AD2-Pad40)") (class "Default")
      (node (ref "U$3") (pin "40") (pinfunction "AD2_40") (pintype "bidirectional"))
    )
    (net (code "178") (name "unconnected-(U$3-AD3-Pad41)") (class "Default")
      (node (ref "U$3") (pin "41") (pinfunction "AD3_41") (pintype "bidirectional"))
    )
    (net (code "179") (name "unconnected-(U$3-AD4-Pad5)") (class "Default")
      (node (ref "U$3") (pin "5") (pinfunction "AD4_5") (pintype "bidirectional"))
    )
    (net (code "180") (name "unconnected-(U$3-AD5-Pad6)") (class "Default")
      (node (ref "U$3") (pin "6") (pinfunction "AD5_6") (pintype "bidirectional"))
    )
    (net (code "181") (name "unconnected-(U$3-AD6-Pad7)") (class "Default")
      (node (ref "U$3") (pin "7") (pinfunction "AD6_7") (pintype "bidirectional"))
    )
    (net (code "182") (name "unconnected-(U$3-AD7-Pad8)") (class "Default")
      (node (ref "U$3") (pin "8") (pinfunction "AD7_8") (pintype "bidirectional"))
    )
    (net (code "183") (name "unconnected-(U$3-AD8-Pad25)") (class "Default")
      (node (ref "U$3") (pin "25") (pinfunction "AD8_25") (pintype "bidirectional"))
    )
    (net (code "184") (name "unconnected-(U$3-AD9-Pad26)") (class "Default")
      (node (ref "U$3") (pin "26") (pinfunction "AD9_26") (pintype "bidirectional"))
    )
    (net (code "185") (name "unconnected-(U$3-AD10-Pad27)") (class "Default")
      (node (ref "U$3") (pin "27") (pinfunction "AD10_27") (pintype "bidirectional"))
    )
    (net (code "186") (name "unconnected-(U$3-AD11-Pad28)") (class "Default")
      (node (ref "U$3") (pin "28") (pinfunction "AD11_28") (pintype "bidirectional"))
    )
    (net (code "187") (name "unconnected-(U$3-AD12-Pad29)") (class "Default")
      (node (ref "U$3") (pin "29") (pinfunction "AD12_29") (pintype "bidirectional"))
    )
    (net (code "188") (name "unconnected-(U$3-AD13-Pad30)") (class "Default")
      (node (ref "U$3") (pin "30") (pinfunction "AD13_30") (pintype "bidirectional"))
    )
    (net (code "189") (name "unconnected-(U$3-AD14-Pad31)") (class "Default")
      (node (ref "U$3") (pin "31") (pinfunction "AD14_31") (pintype "bidirectional"))
    )
    (net (code "190") (name "unconnected-(U$3-CLKOUT-Pad23)") (class "Default")
      (node (ref "U$3") (pin "23") (pinfunction "CLKOUT_23") (pintype "bidirectional"))
    )
    (net (code "191") (name "unconnected-(U$3-PSPCFG0-Pad32)") (class "Default")
      (node (ref "U$3") (pin "32") (pinfunction "PSPCFG0_32") (pintype "bidirectional"))
    )
    (net (code "192") (name "unconnected-(U$5-PA12-Pad22)") (class "Default")
      (node (ref "U$5") (pin "22") (pinfunction "PA12_22") (pintype "bidirectional"))
    )
    (net (code "193") (name "unconnected-(U2-PA0-WKUP-Pad10)") (class "Default")
      (node (ref "U2") (pin "10") (pinfunction "PA0-WKUP_10") (pintype "bidirectional"))
    )
    (net (code "194") (name "unconnected-(U2-PA1-Pad11)") (class "Default")
      (node (ref "U2") (pin "11") (pinfunction "PA1_11") (pintype "bidirectional"))
    )
    (net (code "195") (name "unconnected-(U2-PA15-Pad38)") (class "Default")
      (node (ref "U2") (pin "38") (pinfunction "PA15_38") (pintype "bidirectional"))
    )
    (net (code "196") (name "unconnected-(U2-PB2-Pad20)") (class "Default")
      (node (ref "U2") (pin "20") (pinfunction "PB2_20") (pintype "bidirectional"))
    )
    (net (code "197") (name "unconnected-(U2-PB3-Pad39)") (class "Default")
      (node (ref "U2") (pin "39") (pinfunction "PB3_39") (pintype "bidirectional"))
    )
    (net (code "198") (name "unconnected-(U2-PB4-Pad40)") (class "Default")
      (node (ref "U2") (pin "40") (pinfunction "PB4_40") (pintype "bidirectional"))
    )
    (net (code "199") (name "unconnected-(U2-PB5-Pad41)") (class "Default")
      (node (ref "U2") (pin "41") (pinfunction "PB5_41") (pintype "bidirectional"))
    )
    (net (code "200") (name "unconnected-(U2-PB8-Pad45)") (class "Default")
      (node (ref "U2") (pin "45") (pinfunction "PB8_45") (pintype "bidirectional"))
    )
    (net (code "201") (name "unconnected-(U2-PB9-Pad46)") (class "Default")
      (node (ref "U2") (pin "46") (pinfunction "PB9_46") (pintype "bidirectional"))
    )
    (net (code "202") (name "unconnected-(U2-PC13-TAMPER-RTC-Pad2)") (class "Default")
      (node (ref "U2") (pin "2") (pinfunction "PC13-TAMPER-RTC_2") (pintype "bidirectional"))
    )
    (net (code "203") (name "unconnected-(U4-R2IN-Pad8)") (class "Default")
      (node (ref "U4") (pin "8") (pinfunction "R2IN_8") (pintype "input"))
    )
    (net (code "204") (name "unconnected-(U4-R2OUT-Pad9)") (class "Default")
      (node (ref "U4") (pin "9") (pinfunction "R2OUT_9") (pintype "output"))
    )
    (net (code "205") (name "unconnected-(U4-T2IN-Pad10)") (class "Default")
      (node (ref "U4") (pin "10") (pinfunction "T2IN_10") (pintype "input"))
    )
    (net (code "206") (name "unconnected-(U4-T2OUT-Pad7)") (class "Default")
      (node (ref "U4") (pin "7") (pinfunction "T2OUT_7") (pintype "output"))
    )
    (net (code "207") (name "unconnected-(U5-HOLD_(IO3)-Pad7)") (class "Default")
      (node (ref "U5") (pin "7") (pinfunction "HOLD_(IO3)_7") (pintype "bidirectional"))
    )
    (net (code "208") (name "unconnected-(U5-WP_(IO2)-Pad3)") (class "Default")
      (node (ref "U5") (pin "3") (pinfunction "WP_(IO2)_3") (pintype "bidirectional"))
    )
    (net (code "209") (name "unconnected-(X1-Pad1)") (class "Default")
      (node (ref "X1") (pin "1") (pinfunction "1_1") (pintype "passive"))
    )
    (net (code "210") (name "unconnected-(X1-Pad4)") (class "Default")
      (node (ref "X1") (pin "4") (pinfunction "4_4") (pintype "passive"))
    )
    (net (code "211") (name "unconnected-(X1-Pad6)") (class "Default")
      (node (ref "X1") (pin "6") (pinfunction "6_6") (pintype "passive"))
    )
    (net (code "212") (name "unconnected-(X1-Pad7)") (class "Default")
      (node (ref "X1") (pin "7") (pinfunction "7_7") (pintype "passive"))
    )
    (net (code "213") (name "unconnected-(X1-Pad8)") (class "Default")
      (node (ref "X1") (pin "8") (pinfunction "8_8") (pintype "passive"))
    )
    (net (code "214") (name "unconnected-(X1-Pad9)") (class "Default")
      (node (ref "X1") (pin "9") (pinfunction "9_9") (pintype "passive"))
    )
  )
)
